# servo-ctrl.net
KiCad netlist of a schematic drawn in EAGLE
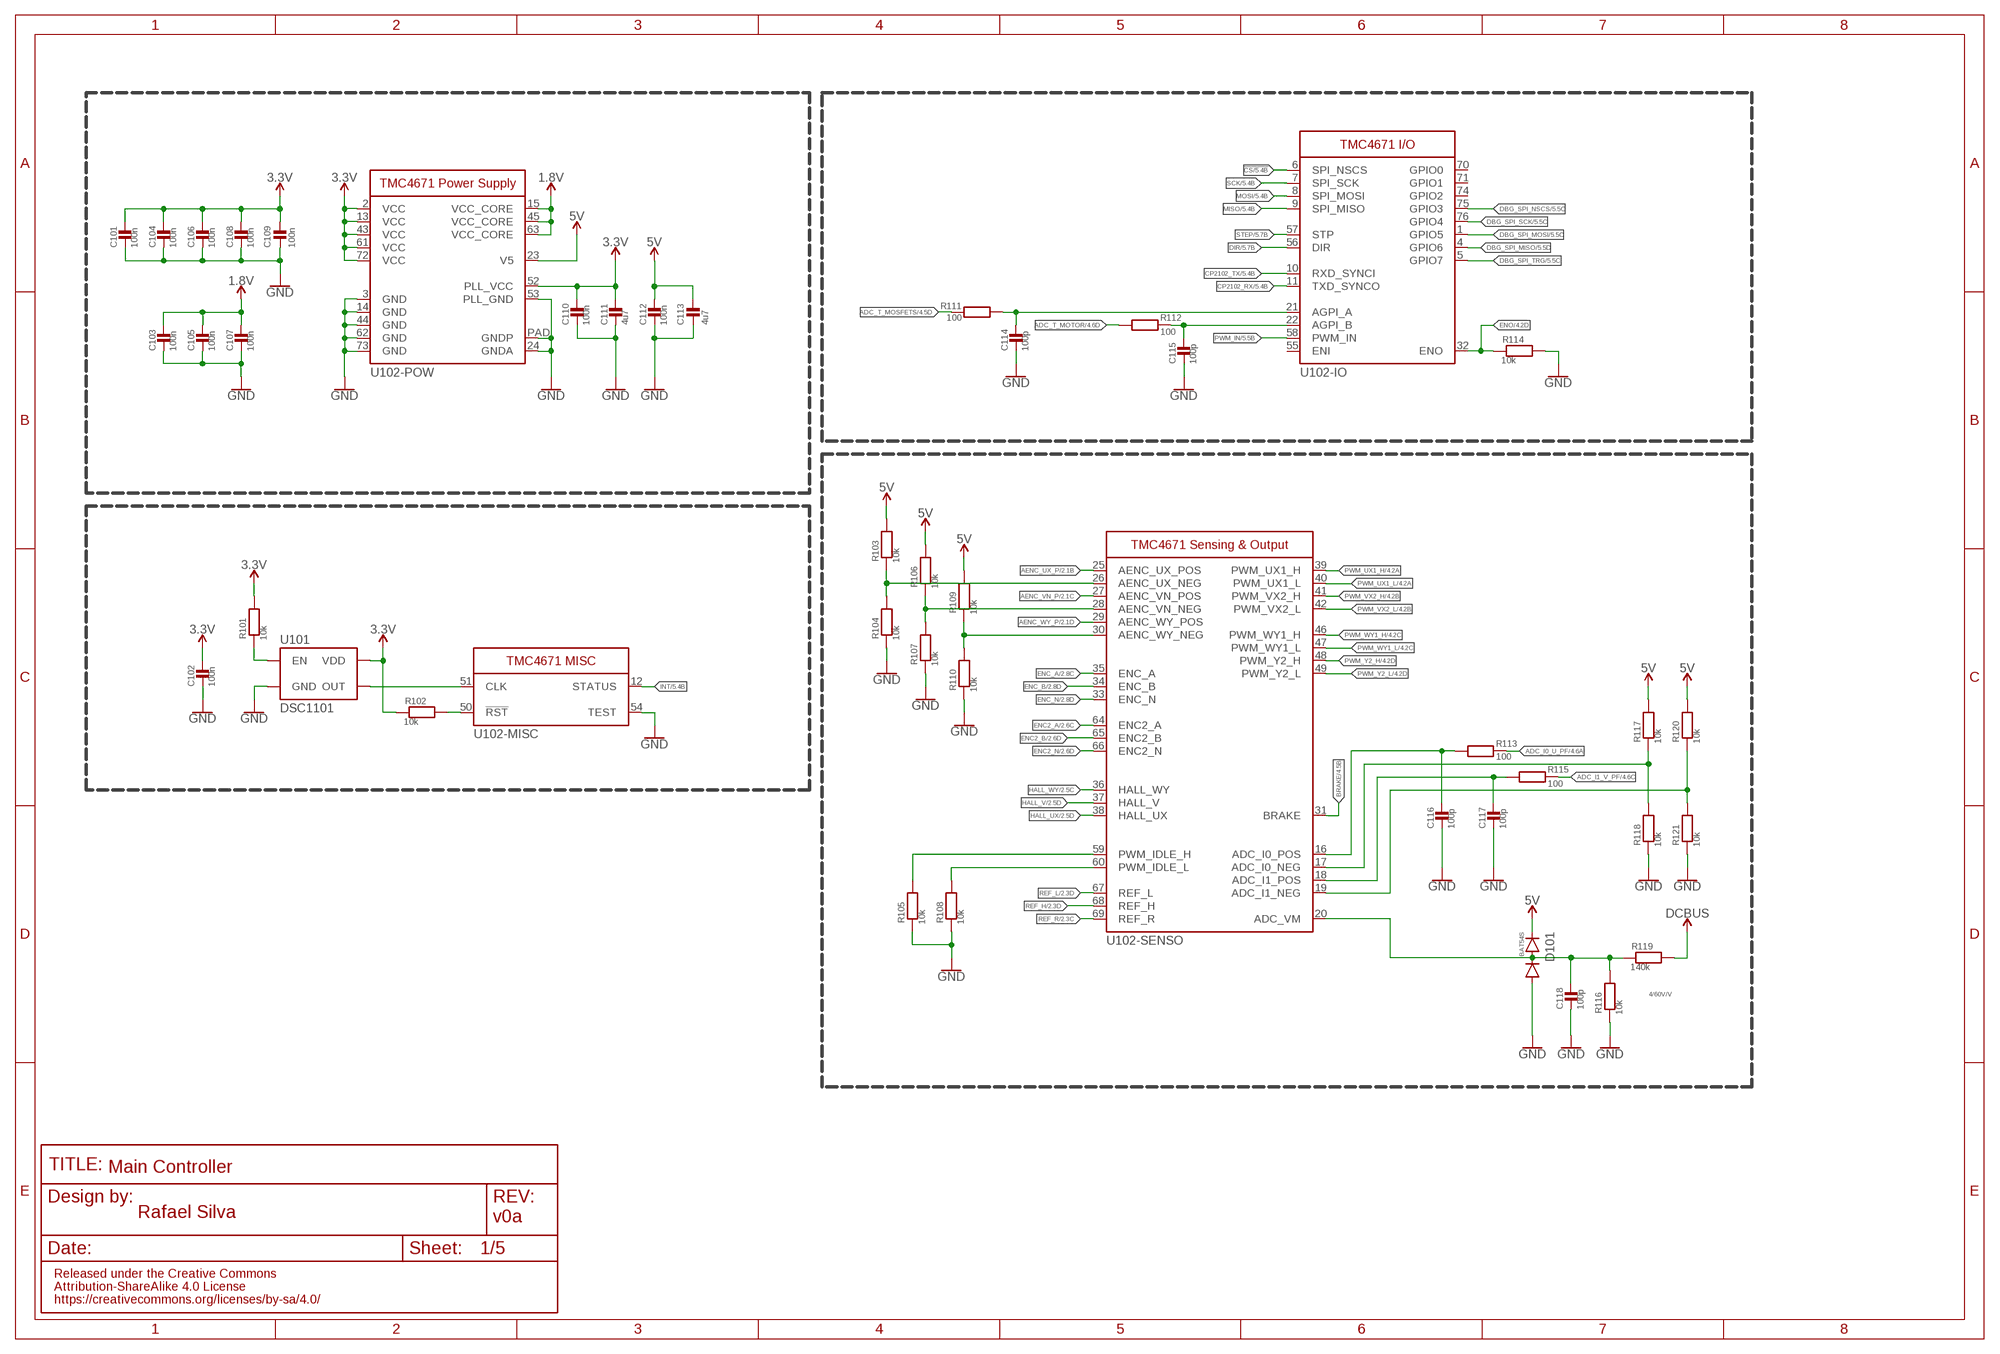
[diagram p0: schematic, sheet 1]
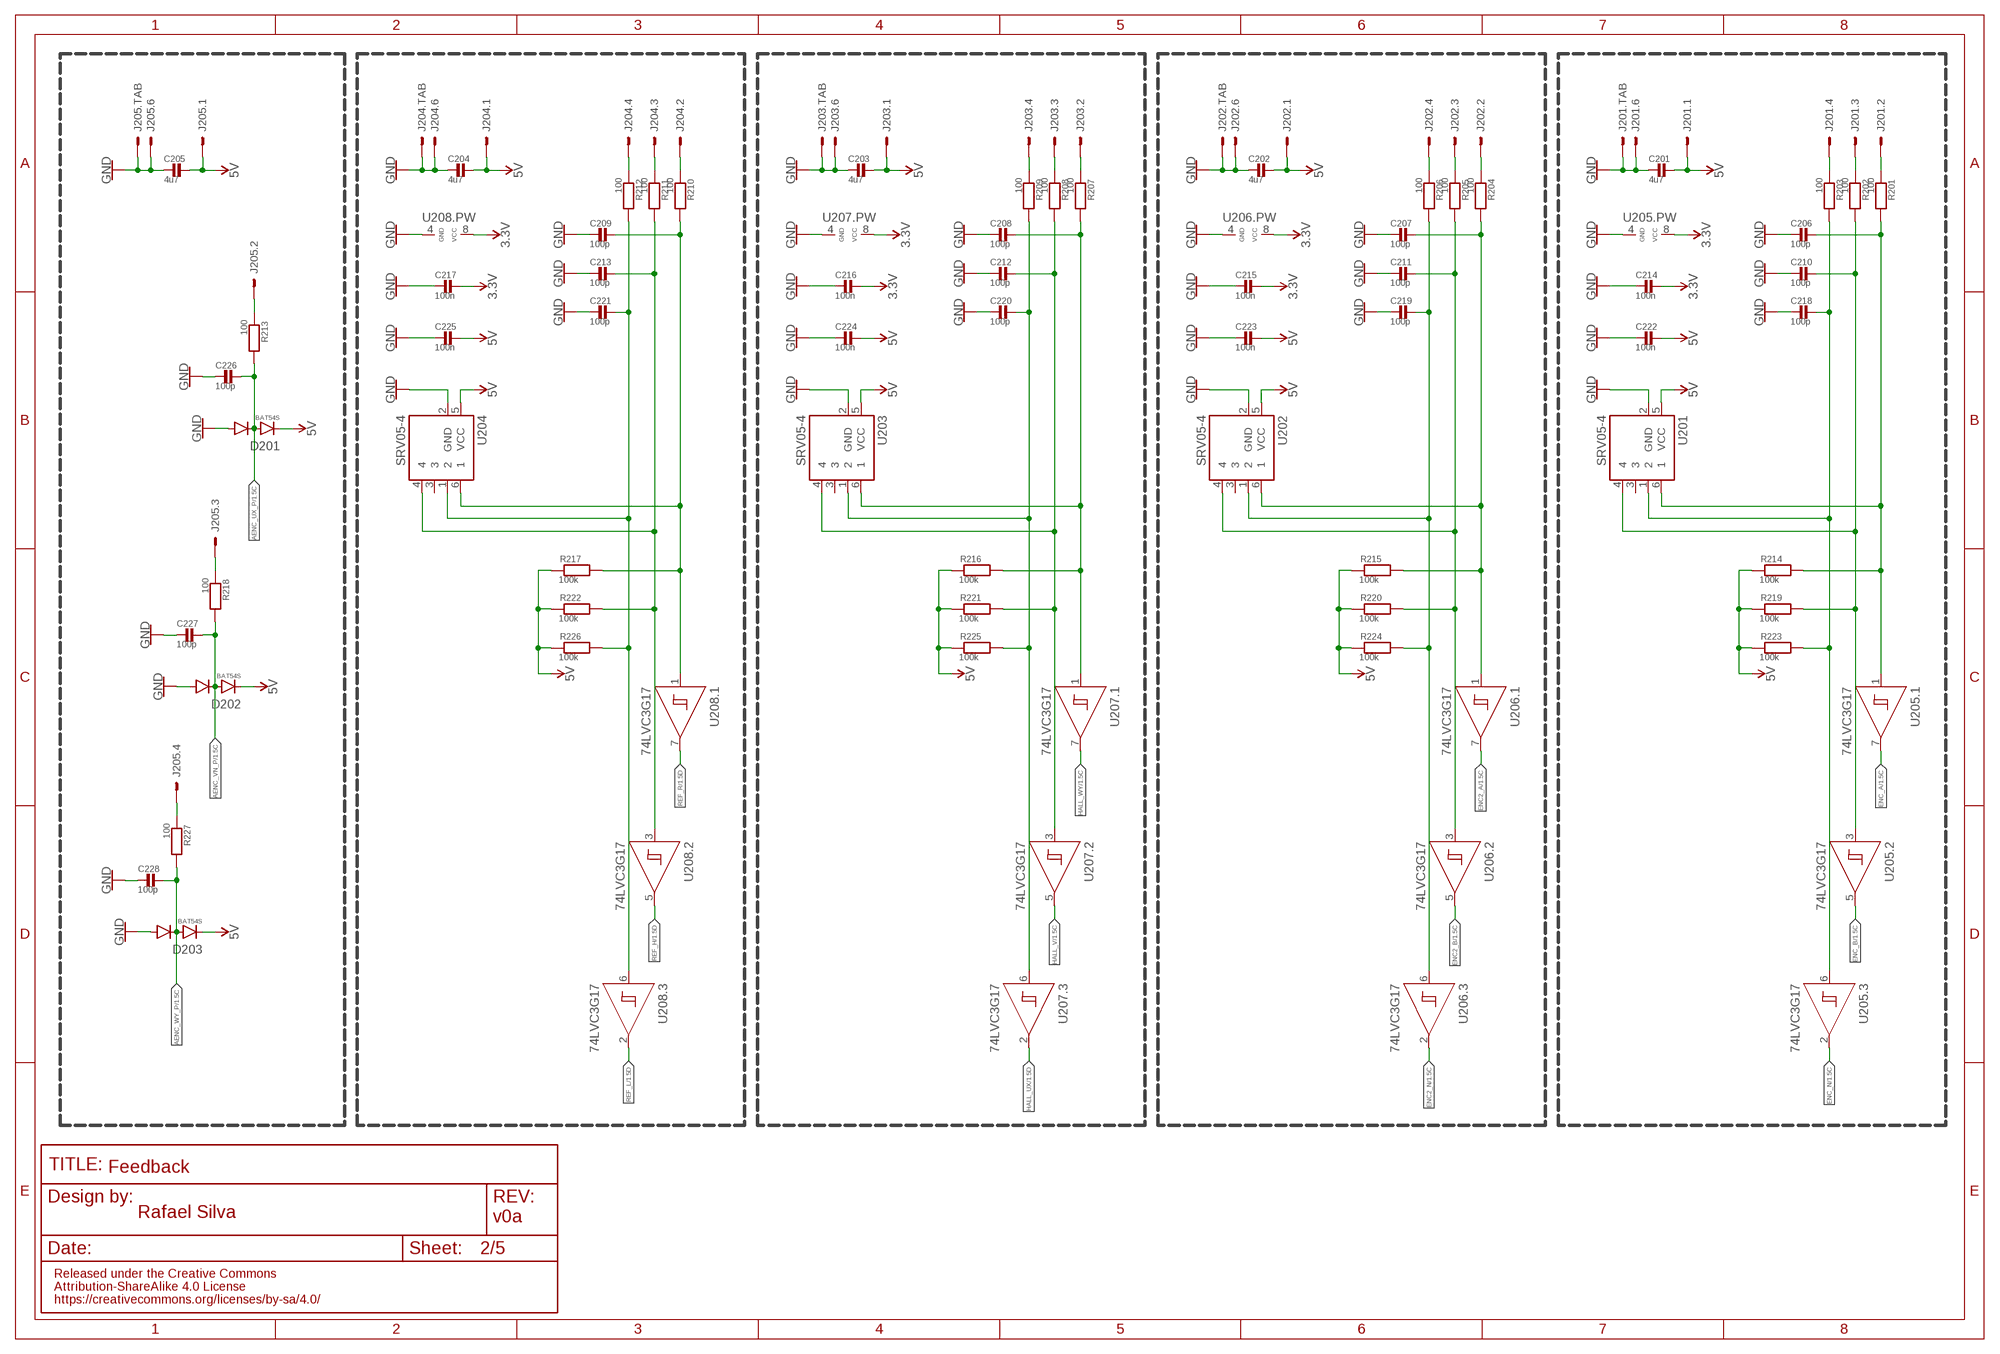
[diagram p1: schematic, sheet 2]
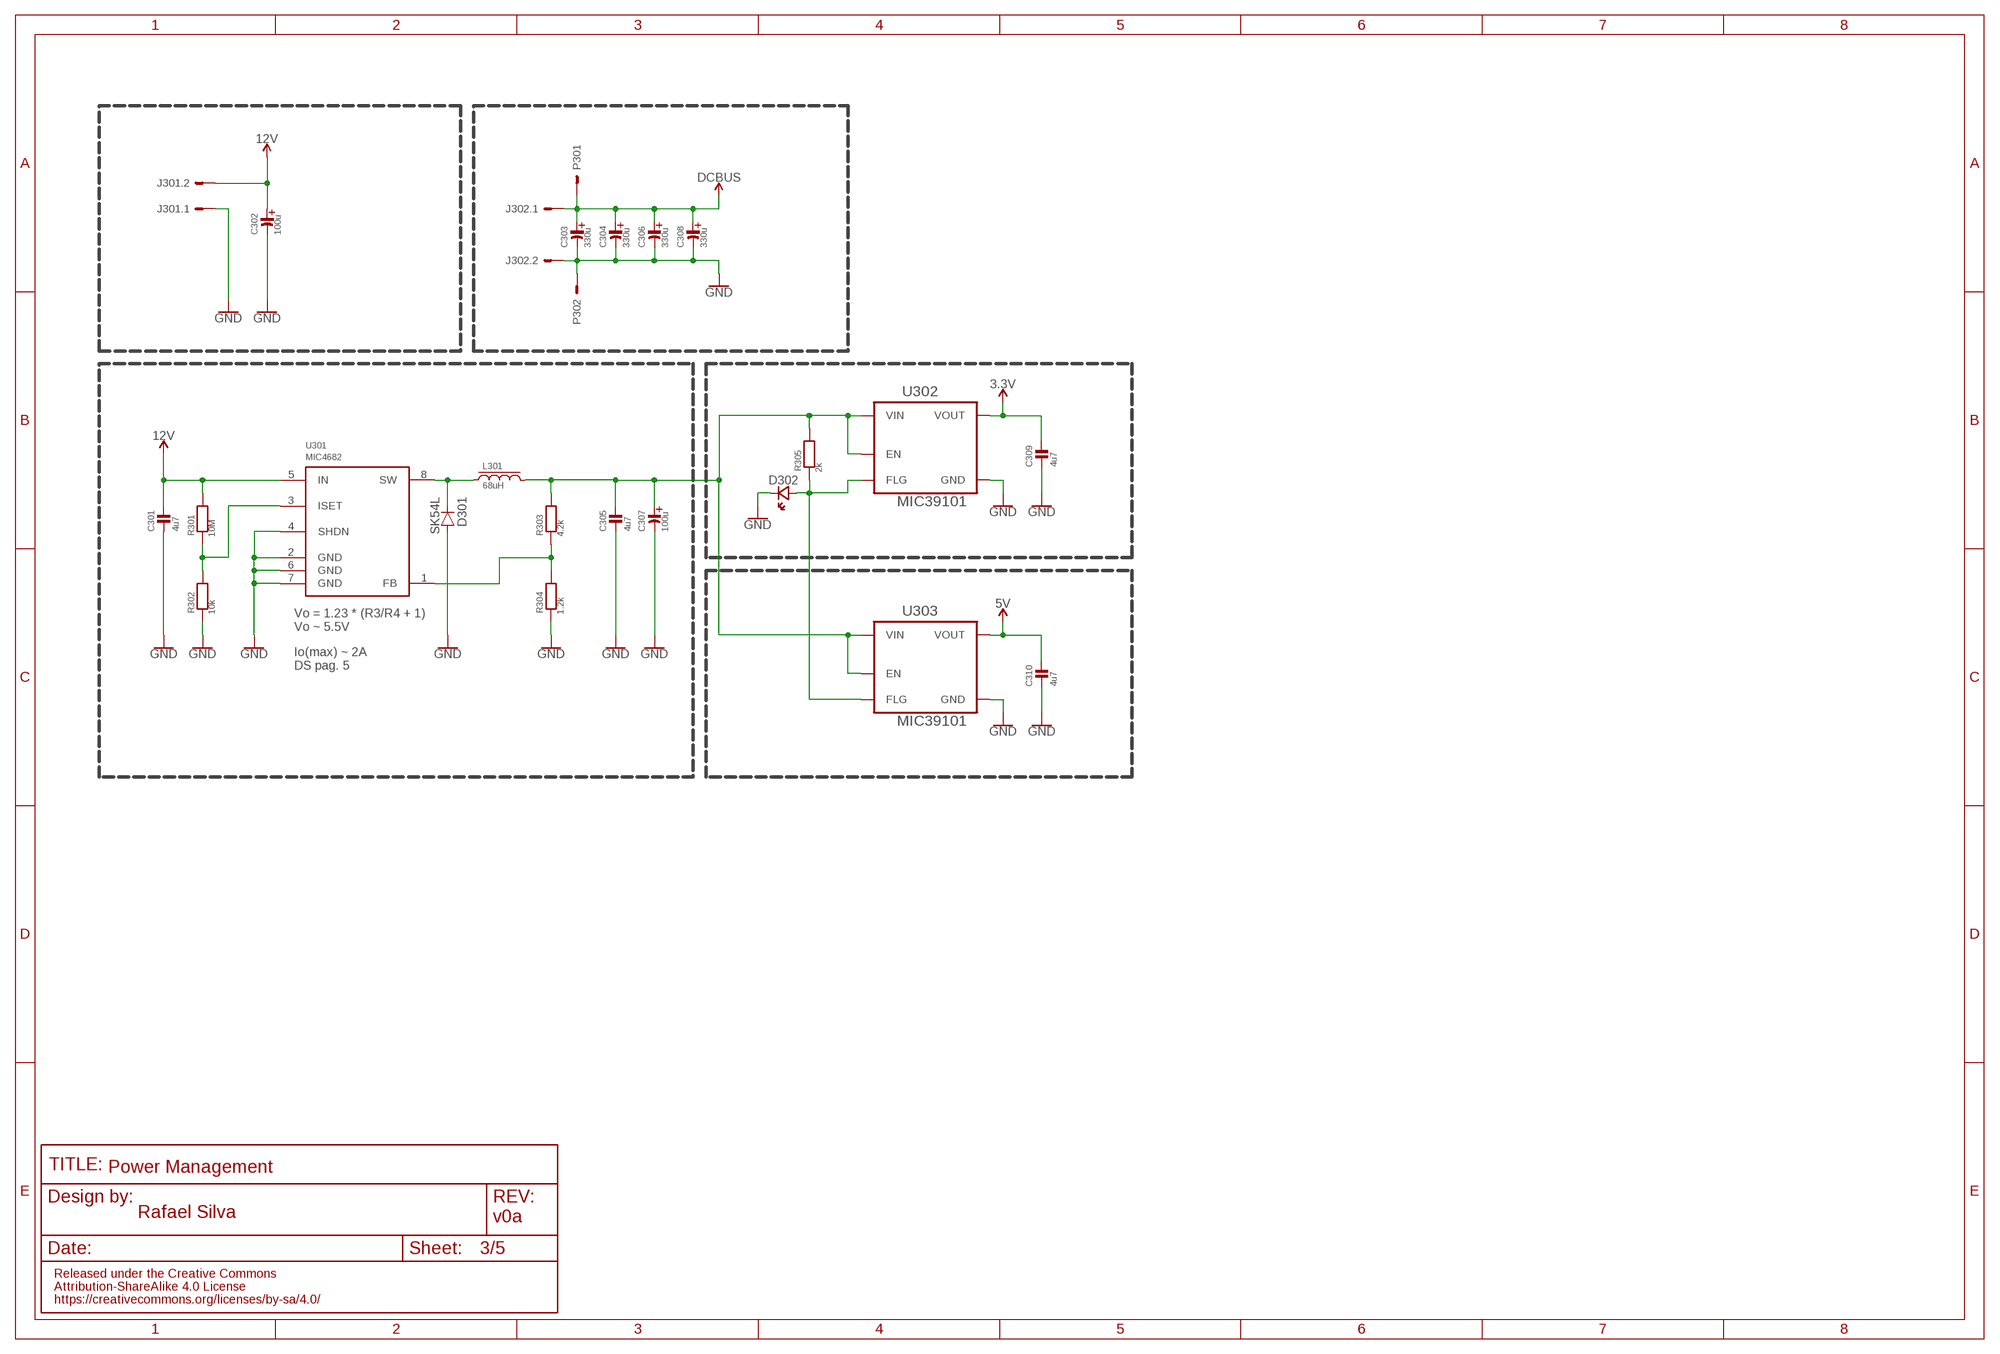
[diagram p2: schematic, sheet 3]
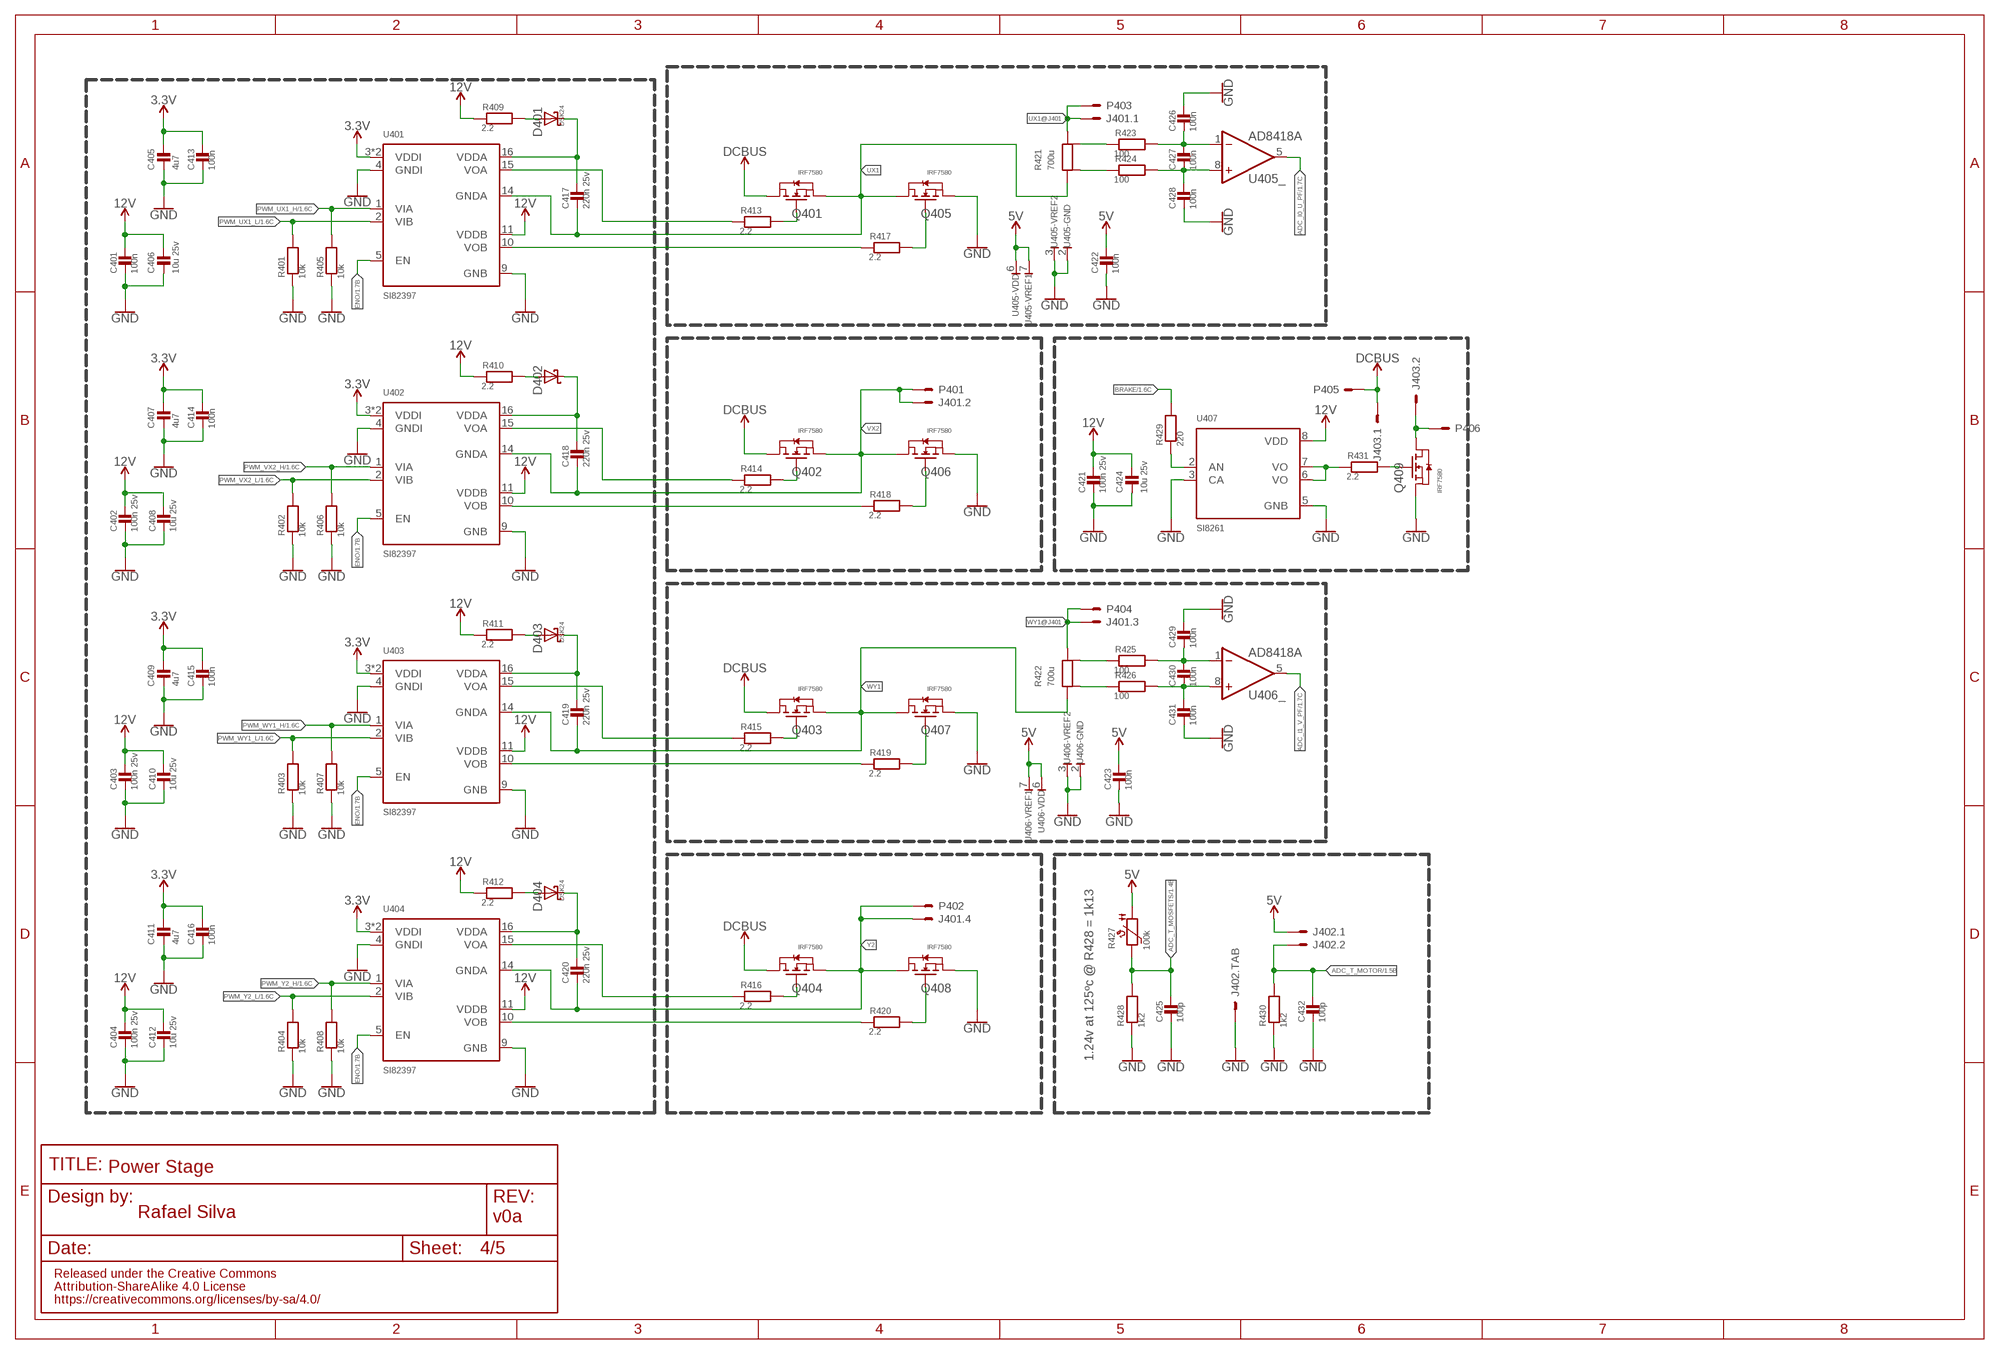
[diagram p3: schematic, sheet 4]
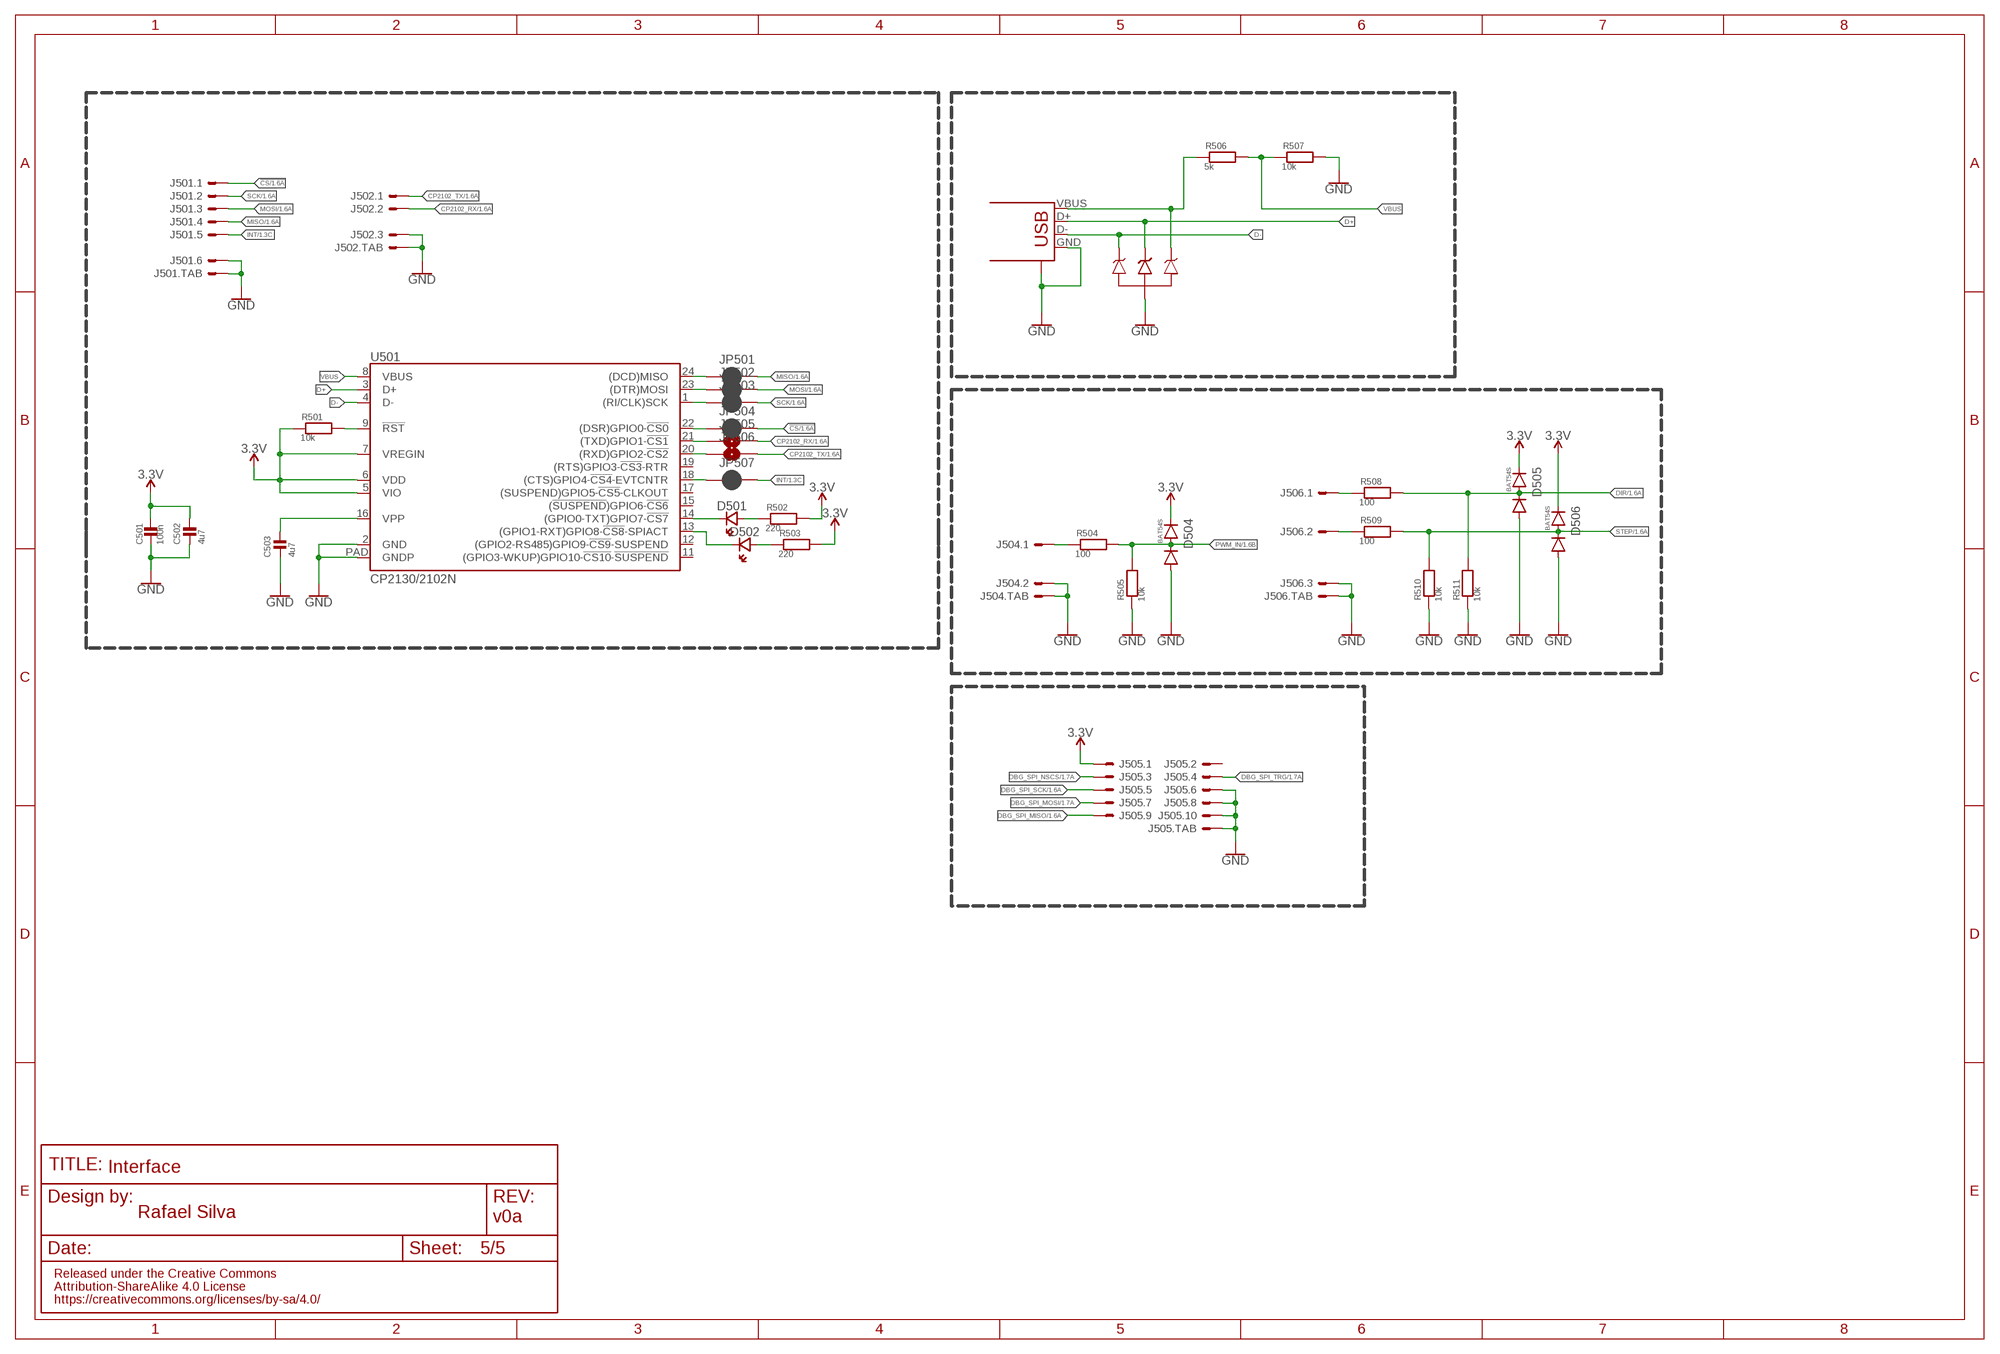
[diagram p4: schematic, sheet 5]

(export (version "E")
  (design (tool "Eeschema 10.0.6"))
  (components
    (comp (ref "C101")
      (value "100n")
      (footprint "eagle-import:0603_WAVE")
      (libsource (lib "eagle-import") (part "MLCC0603"))
    )
    (comp (ref "C102")
      (value "100n")
      (footprint "eagle-import:0603_WAVE")
      (libsource (lib "eagle-import") (part "MLCC0603"))
    )
    (comp (ref "C103")
      (value "100n")
      (footprint "eagle-import:0603_WAVE")
      (libsource (lib "eagle-import") (part "MLCC0603"))
    )
    (comp (ref "C104")
      (value "100n")
      (footprint "eagle-import:0603_WAVE")
      (libsource (lib "eagle-import") (part "MLCC0603"))
    )
    (comp (ref "C105")
      (value "100n")
      (footprint "eagle-import:0603_WAVE")
      (libsource (lib "eagle-import") (part "MLCC0603"))
    )
    (comp (ref "C106")
      (value "100n")
      (footprint "eagle-import:0603_WAVE")
      (libsource (lib "eagle-import") (part "MLCC0603"))
    )
    (comp (ref "C107")
      (value "100n")
      (footprint "eagle-import:0603_WAVE")
      (libsource (lib "eagle-import") (part "MLCC0603"))
    )
    (comp (ref "C108")
      (value "100n")
      (footprint "eagle-import:0603_WAVE")
      (libsource (lib "eagle-import") (part "MLCC0603"))
    )
    (comp (ref "C109")
      (value "100n")
      (footprint "eagle-import:0603_WAVE")
      (libsource (lib "eagle-import") (part "MLCC0603"))
    )
    (comp (ref "C110")
      (value "100n")
      (footprint "eagle-import:0603_WAVE")
      (libsource (lib "eagle-import") (part "MLCC0603"))
    )
    (comp (ref "C111")
      (value "4u7")
      (footprint "eagle-import:0603_WAVE")
      (libsource (lib "eagle-import") (part "MLCC0603"))
    )
    (comp (ref "C112")
      (value "100n")
      (footprint "eagle-import:0603_WAVE")
      (libsource (lib "eagle-import") (part "MLCC0603"))
    )
    (comp (ref "C113")
      (value "4u7")
      (footprint "eagle-import:0603_WAVE")
      (libsource (lib "eagle-import") (part "MLCC0603"))
    )
    (comp (ref "C114")
      (value "100p")
      (footprint "eagle-import:0603_WAVE")
      (libsource (lib "eagle-import") (part "MLCC0603"))
    )
    (comp (ref "C115")
      (value "100p")
      (footprint "eagle-import:0603_WAVE")
      (libsource (lib "eagle-import") (part "MLCC0603"))
    )
    (comp (ref "C116")
      (value "100p")
      (footprint "eagle-import:0603_WAVE")
      (libsource (lib "eagle-import") (part "MLCC0603"))
    )
    (comp (ref "C117")
      (value "100p")
      (footprint "eagle-import:0603_WAVE")
      (libsource (lib "eagle-import") (part "MLCC0603"))
    )
    (comp (ref "C118")
      (value "100p")
      (footprint "eagle-import:0603_WAVE")
      (libsource (lib "eagle-import") (part "MLCC0603"))
    )
    (comp (ref "D101")
      (value "BAT54S")
      (footprint "eagle-import:SOT-23-3")
      (libsource (lib "eagle-import") (part "BAT54S"))
    )
    (comp (ref "R101")
      (value "10k")
      (footprint "eagle-import:0603_WAVE")
      (libsource (lib "eagle-import") (part "RESISTOR0603"))
    )
    (comp (ref "R102")
      (value "10k")
      (footprint "eagle-import:0603_WAVE")
      (libsource (lib "eagle-import") (part "RESISTOR0603"))
    )
    (comp (ref "R103")
      (value "10k")
      (footprint "eagle-import:0603_WAVE")
      (libsource (lib "eagle-import") (part "RESISTOR0603"))
    )
    (comp (ref "R104")
      (value "10k")
      (footprint "eagle-import:0603_WAVE")
      (libsource (lib "eagle-import") (part "RESISTOR0603"))
    )
    (comp (ref "R105")
      (value "10k")
      (footprint "eagle-import:0603_WAVE")
      (libsource (lib "eagle-import") (part "RESISTOR0603"))
    )
    (comp (ref "R106")
      (value "10k")
      (footprint "eagle-import:0603_WAVE")
      (libsource (lib "eagle-import") (part "RESISTOR0603"))
    )
    (comp (ref "R107")
      (value "10k")
      (footprint "eagle-import:0603_WAVE")
      (libsource (lib "eagle-import") (part "RESISTOR0603"))
    )
    (comp (ref "R108")
      (value "10k")
      (footprint "eagle-import:0603_WAVE")
      (libsource (lib "eagle-import") (part "RESISTOR0603"))
    )
    (comp (ref "R109")
      (value "10k")
      (footprint "eagle-import:0603_WAVE")
      (libsource (lib "eagle-import") (part "RESISTOR0603"))
    )
    (comp (ref "R110")
      (value "10k")
      (footprint "eagle-import:0603_WAVE")
      (libsource (lib "eagle-import") (part "RESISTOR0603"))
    )
    (comp (ref "R111")
      (value "100")
      (footprint "eagle-import:0603_WAVE")
      (libsource (lib "eagle-import") (part "RESISTOR0603"))
    )
    (comp (ref "R112")
      (value "100")
      (footprint "eagle-import:0603_WAVE")
      (libsource (lib "eagle-import") (part "RESISTOR0603"))
    )
    (comp (ref "R113")
      (value "100")
      (footprint "eagle-import:0603_WAVE")
      (libsource (lib "eagle-import") (part "RESISTOR0603"))
    )
    (comp (ref "R114")
      (value "10k")
      (footprint "eagle-import:0603_WAVE")
      (libsource (lib "eagle-import") (part "RESISTOR0603"))
    )
    (comp (ref "R115")
      (value "100")
      (footprint "eagle-import:0603_WAVE")
      (libsource (lib "eagle-import") (part "RESISTOR0603"))
    )
    (comp (ref "R116")
      (value "10k")
      (footprint "eagle-import:0603_WAVE")
      (libsource (lib "eagle-import") (part "RESISTOR0603"))
    )
    (comp (ref "R117")
      (value "10k")
      (footprint "eagle-import:0603_WAVE")
      (libsource (lib "eagle-import") (part "RESISTOR0603"))
    )
    (comp (ref "R118")
      (value "10k")
      (footprint "eagle-import:0603_WAVE")
      (libsource (lib "eagle-import") (part "RESISTOR0603"))
    )
    (comp (ref "R119")
      (value "140k")
      (footprint "eagle-import:0603_WAVE")
      (libsource (lib "eagle-import") (part "RESISTOR0603"))
    )
    (comp (ref "R120")
      (value "10k")
      (footprint "eagle-import:0603_WAVE")
      (libsource (lib "eagle-import") (part "RESISTOR0603"))
    )
    (comp (ref "R121")
      (value "10k")
      (footprint "eagle-import:0603_WAVE")
      (libsource (lib "eagle-import") (part "RESISTOR0603"))
    )
    (comp (ref "U101")
      (value "DSC1101")
      (footprint "eagle-import:CDFN_5X3.2")
      (libsource (lib "eagle-import") (part "DSC1101"))
    )
    (comp (ref "U102")
      (value "TMC4671")
      (footprint "eagle-import:QFN76")
      (libsource (lib "eagle-import") (part "TMC4671"))
    )
    (comp (ref "C501")
      (value "100n")
      (footprint "eagle-import:0603_WAVE")
      (libsource (lib "eagle-import") (part "MLCC0603"))
    )
    (comp (ref "C502")
      (value "4u7")
      (footprint "eagle-import:0603_WAVE")
      (libsource (lib "eagle-import") (part "MLCC0603"))
    )
    (comp (ref "C503")
      (value "4u7")
      (footprint "eagle-import:0603_WAVE")
      (libsource (lib "eagle-import") (part "MLCC0603"))
    )
    (comp (ref "D501")
      (value "LED0603")
      (footprint "eagle-import:CHIPLED_0603")
      (libsource (lib "eagle-import") (part "LED0603"))
    )
    (comp (ref "D502")
      (value "LED0603")
      (footprint "eagle-import:CHIPLED_0603")
      (libsource (lib "eagle-import") (part "LED0603"))
    )
    (comp (ref "D503")
      (value "SP0503BAHT")
      (footprint "eagle-import:SOT143")
      (libsource (lib "eagle-import") (part "SP0503BAHT"))
    )
    (comp (ref "D504")
      (value "BAT54S")
      (footprint "eagle-import:SOT-23-3")
      (libsource (lib "eagle-import") (part "BAT54S"))
    )
    (comp (ref "D505")
      (value "BAT54S")
      (footprint "eagle-import:SOT-23-3")
      (libsource (lib "eagle-import") (part "BAT54S"))
    )
    (comp (ref "D506")
      (value "BAT54S")
      (footprint "eagle-import:SOT-23-3")
      (libsource (lib "eagle-import") (part "BAT54S"))
    )
    (comp (ref "J501")
      (value "SH-6")
      (footprint "eagle-import:SM06B-SSR-H-TB")
      (libsource (lib "eagle-import") (part "SH-6"))
    )
    (comp (ref "J502")
      (value "SH-3")
      (footprint "eagle-import:SM03B-SSR-H-TB")
      (libsource (lib "eagle-import") (part "SH-3"))
    )
    (comp (ref "J503")
      (value "USB-SHIELD")
      (footprint "eagle-import:USB-M-S1")
      (libsource (lib "eagle-import") (part "USB-SHIELD"))
    )
    (comp (ref "J504")
      (value "SH-2")
      (footprint "eagle-import:SM02B-SSR-H-TB")
      (libsource (lib "eagle-import") (part "SH-2"))
    )
    (comp (ref "J505")
      (value "F20F-10DP-1V")
      (footprint "eagle-import:F20F-10DP-1V")
      (libsource (lib "eagle-import") (part "F20F-10DP-1V"))
    )
    (comp (ref "J506")
      (value "SH-3")
      (footprint "eagle-import:SM03B-SSR-H-TB")
      (libsource (lib "eagle-import") (part "SH-3"))
    )
    (comp (ref "JP501")
      (value "JUMPER-SMT_2_NC_PASTE_SILK")
      (footprint "eagle-import:SMT-JUMPER_2_NC_PASTE_SILK")
      (libsource (lib "eagle-import") (part "JUMPER-SMT_2_NC_PASTE_SILK"))
    )
    (comp (ref "JP502")
      (value "JUMPER-SMT_2_NC_PASTE_SILK")
      (footprint "eagle-import:SMT-JUMPER_2_NC_PASTE_SILK")
      (libsource (lib "eagle-import") (part "JUMPER-SMT_2_NC_PASTE_SILK"))
    )
    (comp (ref "JP503")
      (value "JUMPER-SMT_2_NC_PASTE_SILK")
      (footprint "eagle-import:SMT-JUMPER_2_NC_PASTE_SILK")
      (libsource (lib "eagle-import") (part "JUMPER-SMT_2_NC_PASTE_SILK"))
    )
    (comp (ref "JP504")
      (value "JUMPER-SMT_2_NC_PASTE_SILK")
      (footprint "eagle-import:SMT-JUMPER_2_NC_PASTE_SILK")
      (libsource (lib "eagle-import") (part "JUMPER-SMT_2_NC_PASTE_SILK"))
    )
    (comp (ref "JP505")
      (value "JUMPER-SMT_2_NO_SILK")
      (footprint "eagle-import:SMT-JUMPER_2_NO_SILK")
      (libsource (lib "eagle-import") (part "JUMPER-SMT_2_NO_SILK"))
    )
    (comp (ref "JP506")
      (value "JUMPER-SMT_2_NO_SILK")
      (footprint "eagle-import:SMT-JUMPER_2_NO_SILK")
      (libsource (lib "eagle-import") (part "JUMPER-SMT_2_NO_SILK"))
    )
    (comp (ref "JP507")
      (value "JUMPER-SMT_2_NC_PASTE_SILK")
      (footprint "eagle-import:SMT-JUMPER_2_NC_PASTE_SILK")
      (libsource (lib "eagle-import") (part "JUMPER-SMT_2_NC_PASTE_SILK"))
    )
    (comp (ref "R501")
      (value "10k")
      (footprint "eagle-import:0603_WAVE")
      (libsource (lib "eagle-import") (part "RESISTOR0603"))
    )
    (comp (ref "R502")
      (value "220")
      (footprint "eagle-import:0603_WAVE")
      (libsource (lib "eagle-import") (part "RESISTOR0603"))
    )
    (comp (ref "R503")
      (value "220")
      (footprint "eagle-import:0603_WAVE")
      (libsource (lib "eagle-import") (part "RESISTOR0603"))
    )
    (comp (ref "R504")
      (value "100")
      (footprint "eagle-import:0603_WAVE")
      (libsource (lib "eagle-import") (part "RESISTOR0603"))
    )
    (comp (ref "R505")
      (value "10k")
      (footprint "eagle-import:0603_WAVE")
      (libsource (lib "eagle-import") (part "RESISTOR0603"))
    )
    (comp (ref "R506")
      (value "5k")
      (footprint "eagle-import:0603_WAVE")
      (libsource (lib "eagle-import") (part "RESISTOR0603"))
    )
    (comp (ref "R507")
      (value "10k")
      (footprint "eagle-import:0603_WAVE")
      (libsource (lib "eagle-import") (part "RESISTOR0603"))
    )
    (comp (ref "R508")
      (value "100")
      (footprint "eagle-import:0603_WAVE")
      (libsource (lib "eagle-import") (part "RESISTOR0603"))
    )
    (comp (ref "R509")
      (value "100")
      (footprint "eagle-import:0603_WAVE")
      (libsource (lib "eagle-import") (part "RESISTOR0603"))
    )
    (comp (ref "R510")
      (value "10k")
      (footprint "eagle-import:0603_WAVE")
      (libsource (lib "eagle-import") (part "RESISTOR0603"))
    )
    (comp (ref "R511")
      (value "10k")
      (footprint "eagle-import:0603_WAVE")
      (libsource (lib "eagle-import") (part "RESISTOR0603"))
    )
    (comp (ref "U501")
      (value "CP2130/2102N")
      (footprint "eagle-import:QFN24")
      (libsource (lib "eagle-import") (part "CP2130/2102N"))
    )
    (comp (ref "C401")
      (value "100n")
      (footprint "eagle-import:0603_WAVE")
      (libsource (lib "eagle-import") (part "MLCC0603"))
    )
    (comp (ref "C402")
      (value "100n 25v")
      (footprint "eagle-import:0603_WAVE")
      (libsource (lib "eagle-import") (part "MLCC0603"))
    )
    (comp (ref "C403")
      (value "100n 25v")
      (footprint "eagle-import:0603_WAVE")
      (libsource (lib "eagle-import") (part "MLCC0603"))
    )
    (comp (ref "C404")
      (value "100n 25v")
      (footprint "eagle-import:0603_WAVE")
      (libsource (lib "eagle-import") (part "MLCC0603"))
    )
    (comp (ref "C405")
      (value "4u7")
      (footprint "eagle-import:0603_WAVE")
      (libsource (lib "eagle-import") (part "MLCC0603"))
    )
    (comp (ref "C406")
      (value "10u 25v")
      (footprint "eagle-import:0603_WAVE")
      (libsource (lib "eagle-import") (part "MLCC0603"))
    )
    (comp (ref "C407")
      (value "4u7")
      (footprint "eagle-import:0603_WAVE")
      (libsource (lib "eagle-import") (part "MLCC0603"))
    )
    (comp (ref "C408")
      (value "10u 25v")
      (footprint "eagle-import:0603_WAVE")
      (libsource (lib "eagle-import") (part "MLCC0603"))
    )
    (comp (ref "C409")
      (value "4u7")
      (footprint "eagle-import:0603_WAVE")
      (libsource (lib "eagle-import") (part "MLCC0603"))
    )
    (comp (ref "C410")
      (value "10u 25v")
      (footprint "eagle-import:0603_WAVE")
      (libsource (lib "eagle-import") (part "MLCC0603"))
    )
    (comp (ref "C411")
      (value "4u7")
      (footprint "eagle-import:0603_WAVE")
      (libsource (lib "eagle-import") (part "MLCC0603"))
    )
    (comp (ref "C412")
      (value "10u 25v")
      (footprint "eagle-import:0603_WAVE")
      (libsource (lib "eagle-import") (part "MLCC0603"))
    )
    (comp (ref "C413")
      (value "100n")
      (footprint "eagle-import:0603_WAVE")
      (libsource (lib "eagle-import") (part "MLCC0603"))
    )
    (comp (ref "C414")
      (value "100n")
      (footprint "eagle-import:0603_WAVE")
      (libsource (lib "eagle-import") (part "MLCC0603"))
    )
    (comp (ref "C415")
      (value "100n")
      (footprint "eagle-import:0603_WAVE")
      (libsource (lib "eagle-import") (part "MLCC0603"))
    )
    (comp (ref "C416")
      (value "100n")
      (footprint "eagle-import:0603_WAVE")
      (libsource (lib "eagle-import") (part "MLCC0603"))
    )
    (comp (ref "C417")
      (value "220n 25v")
      (footprint "eagle-import:0603_WAVE")
      (libsource (lib "eagle-import") (part "MLCC0603"))
    )
    (comp (ref "C418")
      (value "220n 25v")
      (footprint "eagle-import:0603_WAVE")
      (libsource (lib "eagle-import") (part "MLCC0603"))
    )
    (comp (ref "C419")
      (value "220n 25v")
      (footprint "eagle-import:0603_WAVE")
      (libsource (lib "eagle-import") (part "MLCC0603"))
    )
    (comp (ref "C420")
      (value "220n 25v")
      (footprint "eagle-import:0603_WAVE")
      (libsource (lib "eagle-import") (part "MLCC0603"))
    )
    (comp (ref "C421")
      (value "100n 25v")
      (footprint "eagle-import:0603_WAVE")
      (libsource (lib "eagle-import") (part "MLCC0603"))
    )
    (comp (ref "C422")
      (value "100n")
      (footprint "eagle-import:0603_WAVE")
      (libsource (lib "eagle-import") (part "MLCC0603"))
    )
    (comp (ref "C423")
      (value "100n")
      (footprint "eagle-import:0603_WAVE")
      (libsource (lib "eagle-import") (part "MLCC0603"))
    )
    (comp (ref "C424")
      (value "10u 25v")
      (footprint "eagle-import:0603_WAVE")
      (libsource (lib "eagle-import") (part "MLCC0603"))
    )
    (comp (ref "C425")
      (value "100p")
      (footprint "eagle-import:0603_WAVE")
      (libsource (lib "eagle-import") (part "MLCC0603"))
    )
    (comp (ref "C426")
      (value "100n")
      (footprint "eagle-import:0603_WAVE")
      (libsource (lib "eagle-import") (part "MLCC0603"))
    )
    (comp (ref "C427")
      (value "100n")
      (footprint "eagle-import:0603_WAVE")
      (libsource (lib "eagle-import") (part "MLCC0603"))
    )
    (comp (ref "C428")
      (value "100n")
      (footprint "eagle-import:0603_WAVE")
      (libsource (lib "eagle-import") (part "MLCC0603"))
    )
    (comp (ref "C429")
      (value "100n")
      (footprint "eagle-import:0603_WAVE")
      (libsource (lib "eagle-import") (part "MLCC0603"))
    )
    (comp (ref "C430")
      (value "100n")
      (footprint "eagle-import:0603_WAVE")
      (libsource (lib "eagle-import") (part "MLCC0603"))
    )
    (comp (ref "C431")
      (value "100n")
      (footprint "eagle-import:0603_WAVE")
      (libsource (lib "eagle-import") (part "MLCC0603"))
    )
    (comp (ref "C432")
      (value "100p")
      (footprint "eagle-import:0603_WAVE")
      (libsource (lib "eagle-import") (part "MLCC0603"))
    )
    (comp (ref "D401")
      (value "DSK24")
      (footprint "eagle-import:SOD-123")
      (libsource (lib "eagle-import") (part "DSK24"))
    )
    (comp (ref "D402")
      (value "DSK24")
      (footprint "eagle-import:SOD-123")
      (libsource (lib "eagle-import") (part "DSK24"))
    )
    (comp (ref "D403")
      (value "DSK24")
      (footprint "eagle-import:SOD-123")
      (libsource (lib "eagle-import") (part "DSK24"))
    )
    (comp (ref "D404")
      (value "DSK24")
      (footprint "eagle-import:SOD-123")
      (libsource (lib "eagle-import") (part "DSK24"))
    )
    (comp (ref "J401")
      (value "4P-6.35P")
      (footprint "eagle-import:4P-6.35P")
      (libsource (lib "eagle-import") (part "4P-6.35P"))
    )
    (comp (ref "J402")
      (value "SH-2")
      (footprint "eagle-import:SM02B-SSR-H-TB")
      (libsource (lib "eagle-import") (part "SH-2"))
    )
    (comp (ref "J403")
      (value "2P-6.35P")
      (footprint "eagle-import:2P-6.35P")
      (libsource (lib "eagle-import") (part "2P-6.35P"))
    )
    (comp (ref "P401")
      (value "POWPAD")
      (footprint "eagle-import:TH-HP")
      (libsource (lib "eagle-import") (part "POWPAD"))
    )
    (comp (ref "P402")
      (value "POWPAD")
      (footprint "eagle-import:TH-HP")
      (libsource (lib "eagle-import") (part "POWPAD"))
    )
    (comp (ref "P403")
      (value "POWPAD")
      (footprint "eagle-import:TH-HP")
      (libsource (lib "eagle-import") (part "POWPAD"))
    )
    (comp (ref "P404")
      (value "POWPAD")
      (footprint "eagle-import:TH-HP")
      (libsource (lib "eagle-import") (part "POWPAD"))
    )
    (comp (ref "P405")
      (value "POWPAD")
      (footprint "eagle-import:TH-HP")
      (libsource (lib "eagle-import") (part "POWPAD"))
    )
    (comp (ref "P406")
      (value "POWPAD")
      (footprint "eagle-import:TH-HP")
      (libsource (lib "eagle-import") (part "POWPAD"))
    )
    (comp (ref "Q401")
      (value "IRF7580")
      (footprint "eagle-import:DIRECTFET-ME")
      (libsource (lib "eagle-import") (part "IRF7580"))
    )
    (comp (ref "Q402")
      (value "IRF7580")
      (footprint "eagle-import:DIRECTFET-ME")
      (libsource (lib "eagle-import") (part "IRF7580"))
    )
    (comp (ref "Q403")
      (value "IRF7580")
      (footprint "eagle-import:DIRECTFET-ME")
      (libsource (lib "eagle-import") (part "IRF7580"))
    )
    (comp (ref "Q404")
      (value "IRF7580")
      (footprint "eagle-import:DIRECTFET-ME")
      (libsource (lib "eagle-import") (part "IRF7580"))
    )
    (comp (ref "Q405")
      (value "IRF7580")
      (footprint "eagle-import:DIRECTFET-ME")
      (libsource (lib "eagle-import") (part "IRF7580"))
    )
    (comp (ref "Q406")
      (value "IRF7580")
      (footprint "eagle-import:DIRECTFET-ME")
      (libsource (lib "eagle-import") (part "IRF7580"))
    )
    (comp (ref "Q407")
      (value "IRF7580")
      (footprint "eagle-import:DIRECTFET-ME")
      (libsource (lib "eagle-import") (part "IRF7580"))
    )
    (comp (ref "Q408")
      (value "IRF7580")
      (footprint "eagle-import:DIRECTFET-ME")
      (libsource (lib "eagle-import") (part "IRF7580"))
    )
    (comp (ref "Q409")
      (value "IRF7580")
      (footprint "eagle-import:DIRECTFET-ME")
      (libsource (lib "eagle-import") (part "IRF7580"))
    )
    (comp (ref "R401")
      (value "10k")
      (footprint "eagle-import:0603_WAVE")
      (libsource (lib "eagle-import") (part "RESISTOR0603"))
    )
    (comp (ref "R402")
      (value "10k")
      (footprint "eagle-import:0603_WAVE")
      (libsource (lib "eagle-import") (part "RESISTOR0603"))
    )
    (comp (ref "R403")
      (value "10k")
      (footprint "eagle-import:0603_WAVE")
      (libsource (lib "eagle-import") (part "RESISTOR0603"))
    )
    (comp (ref "R404")
      (value "10k")
      (footprint "eagle-import:0603_WAVE")
      (libsource (lib "eagle-import") (part "RESISTOR0603"))
    )
    (comp (ref "R405")
      (value "10k")
      (footprint "eagle-import:0603_WAVE")
      (libsource (lib "eagle-import") (part "RESISTOR0603"))
    )
    (comp (ref "R406")
      (value "10k")
      (footprint "eagle-import:0603_WAVE")
      (libsource (lib "eagle-import") (part "RESISTOR0603"))
    )
    (comp (ref "R407")
      (value "10k")
      (footprint "eagle-import:0603_WAVE")
      (libsource (lib "eagle-import") (part "RESISTOR0603"))
    )
    (comp (ref "R408")
      (value "10k")
      (footprint "eagle-import:0603_WAVE")
      (libsource (lib "eagle-import") (part "RESISTOR0603"))
    )
    (comp (ref "R409")
      (value "2.2")
      (footprint "eagle-import:0603_WAVE")
      (libsource (lib "eagle-import") (part "RESISTOR0603"))
    )
    (comp (ref "R410")
      (value "2.2")
      (footprint "eagle-import:0603_WAVE")
      (libsource (lib "eagle-import") (part "RESISTOR0603"))
    )
    (comp (ref "R411")
      (value "2.2")
      (footprint "eagle-import:0603_WAVE")
      (libsource (lib "eagle-import") (part "RESISTOR0603"))
    )
    (comp (ref "R412")
      (value "2.2")
      (footprint "eagle-import:0603_WAVE")
      (libsource (lib "eagle-import") (part "RESISTOR0603"))
    )
    (comp (ref "R413")
      (value "2.2")
      (footprint "eagle-import:0603_WAVE")
      (libsource (lib "eagle-import") (part "RESISTOR0603"))
    )
    (comp (ref "R414")
      (value "2.2")
      (footprint "eagle-import:0603_WAVE")
      (libsource (lib "eagle-import") (part "RESISTOR0603"))
    )
    (comp (ref "R415")
      (value "2.2")
      (footprint "eagle-import:0603_WAVE")
      (libsource (lib "eagle-import") (part "RESISTOR0603"))
    )
    (comp (ref "R416")
      (value "2.2")
      (footprint "eagle-import:0603_WAVE")
      (libsource (lib "eagle-import") (part "RESISTOR0603"))
    )
    (comp (ref "R417")
      (value "2.2")
      (footprint "eagle-import:0603_WAVE")
      (libsource (lib "eagle-import") (part "RESISTOR0603"))
    )
    (comp (ref "R418")
      (value "2.2")
      (footprint "eagle-import:0603_WAVE")
      (libsource (lib "eagle-import") (part "RESISTOR0603"))
    )
    (comp (ref "R419")
      (value "2.2")
      (footprint "eagle-import:0603_WAVE")
      (libsource (lib "eagle-import") (part "RESISTOR0603"))
    )
    (comp (ref "R420")
      (value "2.2")
      (footprint "eagle-import:0603_WAVE")
      (libsource (lib "eagle-import") (part "RESISTOR0603"))
    )
    (comp (ref "R421")
      (value "700u")
      (footprint "eagle-import:3920")
      (libsource (lib "eagle-import") (part "LRMAP3920"))
    )
    (comp (ref "R422")
      (value "700u")
      (footprint "eagle-import:3920")
      (libsource (lib "eagle-import") (part "LRMAP3920"))
    )
    (comp (ref "R423")
      (value "100")
      (footprint "eagle-import:0603_WAVE")
      (libsource (lib "eagle-import") (part "RESISTOR0603"))
    )
    (comp (ref "R424")
      (value "100")
      (footprint "eagle-import:0603_WAVE")
      (libsource (lib "eagle-import") (part "RESISTOR0603"))
    )
    (comp (ref "R425")
      (value "100")
      (footprint "eagle-import:0603_WAVE")
      (libsource (lib "eagle-import") (part "RESISTOR0603"))
    )
    (comp (ref "R426")
      (value "100")
      (footprint "eagle-import:0603_WAVE")
      (libsource (lib "eagle-import") (part "RESISTOR0603"))
    )
    (comp (ref "R427")
      (value "100k")
      (footprint "eagle-import:0603_WAVE")
      (libsource (lib "eagle-import") (part "NTC0603"))
    )
    (comp (ref "R428")
      (value "1k2")
      (footprint "eagle-import:0603_WAVE")
      (libsource (lib "eagle-import") (part "RESISTOR0603"))
    )
    (comp (ref "R429")
      (value "220")
      (footprint "eagle-import:0603_WAVE")
      (libsource (lib "eagle-import") (part "RESISTOR0603"))
    )
    (comp (ref "R430")
      (value "1k2")
      (footprint "eagle-import:0603_WAVE")
      (libsource (lib "eagle-import") (part "RESISTOR0603"))
    )
    (comp (ref "R431")
      (value "2.2")
      (footprint "eagle-import:0603_WAVE")
      (libsource (lib "eagle-import") (part "RESISTOR0603"))
    )
    (comp (ref "U401")
      (value "SI82397")
      (footprint "eagle-import:SOIC-16-WB")
      (libsource (lib "eagle-import") (part "SI82397"))
    )
    (comp (ref "U402")
      (value "SI82397")
      (footprint "eagle-import:SOIC-16-WB")
      (libsource (lib "eagle-import") (part "SI82397"))
    )
    (comp (ref "U403")
      (value "SI82397")
      (footprint "eagle-import:SOIC-16-WB")
      (libsource (lib "eagle-import") (part "SI82397"))
    )
    (comp (ref "U404")
      (value "SI82397")
      (footprint "eagle-import:SOIC-16-WB")
      (libsource (lib "eagle-import") (part "SI82397"))
    )
    (comp (ref "U405")
      (value "AD8418A")
      (footprint "eagle-import:MSOP-8")
      (libsource (lib "eagle-import") (part "AD8418A"))
    )
    (comp (ref "U406")
      (value "AD8418A")
      (footprint "eagle-import:MSOP-8")
      (libsource (lib "eagle-import") (part "AD8418A"))
    )
    (comp (ref "U407")
      (value "SI8261")
      (footprint "eagle-import:SOIC_8")
      (libsource (lib "eagle-import") (part "SI8261"))
    )
    (comp (ref "C301")
      (value "4u7")
      (footprint "eagle-import:0603_WAVE")
      (libsource (lib "eagle-import") (part "MLCC0603"))
    )
    (comp (ref "C302")
      (value "100u")
      (footprint "eagle-import:PANASONIC_D")
      (libsource (lib "eagle-import") (part "CAPACITOR_ELD"))
    )
    (comp (ref "C303")
      (value "330u")
      (footprint "eagle-import:PANASONIC_G")
      (libsource (lib "eagle-import") (part "CAPACITOR_ELG"))
    )
    (comp (ref "C304")
      (value "330u")
      (footprint "eagle-import:PANASONIC_G")
      (libsource (lib "eagle-import") (part "CAPACITOR_ELG"))
    )
    (comp (ref "C305")
      (value "4u7")
      (footprint "eagle-import:0603_WAVE")
      (libsource (lib "eagle-import") (part "MLCC0603"))
    )
    (comp (ref "C306")
      (value "330u")
      (footprint "eagle-import:PANASONIC_G")
      (libsource (lib "eagle-import") (part "CAPACITOR_ELG"))
    )
    (comp (ref "C307")
      (value "100u")
      (footprint "eagle-import:PANASONIC_D")
      (libsource (lib "eagle-import") (part "CAPACITOR_ELD"))
    )
    (comp (ref "C308")
      (value "330u")
      (footprint "eagle-import:PANASONIC_G")
      (libsource (lib "eagle-import") (part "CAPACITOR_ELG"))
    )
    (comp (ref "C309")
      (value "4u7")
      (footprint "eagle-import:0603_WAVE")
      (libsource (lib "eagle-import") (part "MLCC0603"))
    )
    (comp (ref "C310")
      (value "4u7")
      (footprint "eagle-import:0603_WAVE")
      (libsource (lib "eagle-import") (part "MLCC0603"))
    )
    (comp (ref "D301")
      (value "SK54L")
      (footprint "eagle-import:DO214AA")
      (libsource (lib "eagle-import") (part "SK54L"))
    )
    (comp (ref "D302")
      (value "LED0603")
      (footprint "eagle-import:CHIPLED_0603")
      (libsource (lib "eagle-import") (part "LED0603"))
    )
    (comp (ref "J301")
      (value "2P-6.35P")
      (footprint "eagle-import:2P-6.35P")
      (libsource (lib "eagle-import") (part "2P-6.35P"))
    )
    (comp (ref "J302")
      (value "2P-6.35P")
      (footprint "eagle-import:2P-6.35P")
      (libsource (lib "eagle-import") (part "2P-6.35P"))
    )
    (comp (ref "L301")
      (value "68uH")
      (footprint "eagle-import:CDRH104R")
      (libsource (lib "eagle-import") (part "INDUCTORCDRH104R"))
    )
    (comp (ref "P301")
      (value "POWPAD")
      (footprint "eagle-import:TH-HP")
      (libsource (lib "eagle-import") (part "POWPAD"))
    )
    (comp (ref "P302")
      (value "POWPAD")
      (footprint "eagle-import:TH-HP")
      (libsource (lib "eagle-import") (part "POWPAD"))
    )
    (comp (ref "R301")
      (value "10M")
      (footprint "eagle-import:0603_WAVE")
      (libsource (lib "eagle-import") (part "RESISTOR0603"))
    )
    (comp (ref "R302")
      (value "10k")
      (footprint "eagle-import:0603_WAVE")
      (libsource (lib "eagle-import") (part "RESISTOR0603"))
    )
    (comp (ref "R303")
      (value "4.2k")
      (footprint "eagle-import:0603_WAVE")
      (libsource (lib "eagle-import") (part "RESISTOR0603"))
    )
    (comp (ref "R304")
      (value "1.2k")
      (footprint "eagle-import:0603_WAVE")
      (libsource (lib "eagle-import") (part "RESISTOR0603"))
    )
    (comp (ref "R305")
      (value "2k")
      (footprint "eagle-import:0603_WAVE")
      (libsource (lib "eagle-import") (part "RESISTOR0603"))
    )
    (comp (ref "U301")
      (value "MIC4682")
      (footprint "eagle-import:SOIC8")
      (libsource (lib "eagle-import") (part "MIC4682"))
    )
    (comp (ref "U302")
      (value "MIC39101")
      (footprint "eagle-import:SOIC8")
      (libsource (lib "eagle-import") (part "MIC39101"))
    )
    (comp (ref "U303")
      (value "MIC39101")
      (footprint "eagle-import:SOIC8")
      (libsource (lib "eagle-import") (part "MIC39101"))
    )
    (comp (ref "C201")
      (value "4u7")
      (footprint "eagle-import:0603_WAVE")
      (libsource (lib "eagle-import") (part "MLCC0603"))
    )
    (comp (ref "C202")
      (value "4u7")
      (footprint "eagle-import:0603_WAVE")
      (libsource (lib "eagle-import") (part "MLCC0603"))
    )
    (comp (ref "C203")
      (value "4u7")
      (footprint "eagle-import:0603_WAVE")
      (libsource (lib "eagle-import") (part "MLCC0603"))
    )
    (comp (ref "C204")
      (value "4u7")
      (footprint "eagle-import:0603_WAVE")
      (libsource (lib "eagle-import") (part "MLCC0603"))
    )
    (comp (ref "C205")
      (value "4u7")
      (footprint "eagle-import:0603_WAVE")
      (libsource (lib "eagle-import") (part "MLCC0603"))
    )
    (comp (ref "C206")
      (value "100p")
      (footprint "eagle-import:0603_WAVE")
      (libsource (lib "eagle-import") (part "MLCC0603"))
    )
    (comp (ref "C207")
      (value "100p")
      (footprint "eagle-import:0603_WAVE")
      (libsource (lib "eagle-import") (part "MLCC0603"))
    )
    (comp (ref "C208")
      (value "100p")
      (footprint "eagle-import:0603_WAVE")
      (libsource (lib "eagle-import") (part "MLCC0603"))
    )
    (comp (ref "C209")
      (value "100p")
      (footprint "eagle-import:0603_WAVE")
      (libsource (lib "eagle-import") (part "MLCC0603"))
    )
    (comp (ref "C210")
      (value "100p")
      (footprint "eagle-import:0603_WAVE")
      (libsource (lib "eagle-import") (part "MLCC0603"))
    )
    (comp (ref "C211")
      (value "100p")
      (footprint "eagle-import:0603_WAVE")
      (libsource (lib "eagle-import") (part "MLCC0603"))
    )
    (comp (ref "C212")
      (value "100p")
      (footprint "eagle-import:0603_WAVE")
      (libsource (lib "eagle-import") (part "MLCC0603"))
    )
    (comp (ref "C213")
      (value "100p")
      (footprint "eagle-import:0603_WAVE")
      (libsource (lib "eagle-import") (part "MLCC0603"))
    )
    (comp (ref "C214")
      (value "100n")
      (footprint "eagle-import:0603_WAVE")
      (libsource (lib "eagle-import") (part "MLCC0603"))
    )
    (comp (ref "C215")
      (value "100n")
      (footprint "eagle-import:0603_WAVE")
      (libsource (lib "eagle-import") (part "MLCC0603"))
    )
    (comp (ref "C216")
      (value "100n")
      (footprint "eagle-import:0603_WAVE")
      (libsource (lib "eagle-import") (part "MLCC0603"))
    )
    (comp (ref "C217")
      (value "100n")
      (footprint "eagle-import:0603_WAVE")
      (libsource (lib "eagle-import") (part "MLCC0603"))
    )
    (comp (ref "C218")
      (value "100p")
      (footprint "eagle-import:0603_WAVE")
      (libsource (lib "eagle-import") (part "MLCC0603"))
    )
    (comp (ref "C219")
      (value "100p")
      (footprint "eagle-import:0603_WAVE")
      (libsource (lib "eagle-import") (part "MLCC0603"))
    )
    (comp (ref "C220")
      (value "100p")
      (footprint "eagle-import:0603_WAVE")
      (libsource (lib "eagle-import") (part "MLCC0603"))
    )
    (comp (ref "C221")
      (value "100p")
      (footprint "eagle-import:0603_WAVE")
      (libsource (lib "eagle-import") (part "MLCC0603"))
    )
    (comp (ref "C222")
      (value "100n")
      (footprint "eagle-import:0603_WAVE")
      (libsource (lib "eagle-import") (part "MLCC0603"))
    )
    (comp (ref "C223")
      (value "100n")
      (footprint "eagle-import:0603_WAVE")
      (libsource (lib "eagle-import") (part "MLCC0603"))
    )
    (comp (ref "C224")
      (value "100n")
      (footprint "eagle-import:0603_WAVE")
      (libsource (lib "eagle-import") (part "MLCC0603"))
    )
    (comp (ref "C225")
      (value "100n")
      (footprint "eagle-import:0603_WAVE")
      (libsource (lib "eagle-import") (part "MLCC0603"))
    )
    (comp (ref "C226")
      (value "100p")
      (footprint "eagle-import:0603_WAVE")
      (libsource (lib "eagle-import") (part "MLCC0603"))
    )
    (comp (ref "C227")
      (value "100p")
      (footprint "eagle-import:0603_WAVE")
      (libsource (lib "eagle-import") (part "MLCC0603"))
    )
    (comp (ref "C228")
      (value "100p")
      (footprint "eagle-import:0603_WAVE")
      (libsource (lib "eagle-import") (part "MLCC0603"))
    )
    (comp (ref "D201")
      (value "BAT54S")
      (footprint "eagle-import:SOT-23-3")
      (libsource (lib "eagle-import") (part "BAT54S"))
    )
    (comp (ref "D202")
      (value "BAT54S")
      (footprint "eagle-import:SOT-23-3")
      (libsource (lib "eagle-import") (part "BAT54S"))
    )
    (comp (ref "D203")
      (value "BAT54S")
      (footprint "eagle-import:SOT-23-3")
      (libsource (lib "eagle-import") (part "BAT54S"))
    )
    (comp (ref "J201")
      (value "SH-5")
      (footprint "eagle-import:SM05B-SSR-H-TB")
      (libsource (lib "eagle-import") (part "SH-5"))
    )
    (comp (ref "J202")
      (value "SH-5")
      (footprint "eagle-import:SM05B-SSR-H-TB")
      (libsource (lib "eagle-import") (part "SH-5"))
    )
    (comp (ref "J203")
      (value "SH-5")
      (footprint "eagle-import:SM05B-SSR-H-TB")
      (libsource (lib "eagle-import") (part "SH-5"))
    )
    (comp (ref "J204")
      (value "SH-5")
      (footprint "eagle-import:SM05B-SSR-H-TB")
      (libsource (lib "eagle-import") (part "SH-5"))
    )
    (comp (ref "J205")
      (value "SH-5")
      (footprint "eagle-import:SM05B-SSR-H-TB")
      (libsource (lib "eagle-import") (part "SH-5"))
    )
    (comp (ref "R201")
      (value "100")
      (footprint "eagle-import:0603_WAVE")
      (libsource (lib "eagle-import") (part "RESISTOR0603"))
    )
    (comp (ref "R202")
      (value "100")
      (footprint "eagle-import:0603_WAVE")
      (libsource (lib "eagle-import") (part "RESISTOR0603"))
    )
    (comp (ref "R203")
      (value "100")
      (footprint "eagle-import:0603_WAVE")
      (libsource (lib "eagle-import") (part "RESISTOR0603"))
    )
    (comp (ref "R204")
      (value "100")
      (footprint "eagle-import:0603_WAVE")
      (libsource (lib "eagle-import") (part "RESISTOR0603"))
    )
    (comp (ref "R205")
      (value "100")
      (footprint "eagle-import:0603_WAVE")
      (libsource (lib "eagle-import") (part "RESISTOR0603"))
    )
    (comp (ref "R206")
      (value "100")
      (footprint "eagle-import:0603_WAVE")
      (libsource (lib "eagle-import") (part "RESISTOR0603"))
    )
    (comp (ref "R207")
      (value "100")
      (footprint "eagle-import:0603_WAVE")
      (libsource (lib "eagle-import") (part "RESISTOR0603"))
    )
    (comp (ref "R208")
      (value "100")
      (footprint "eagle-import:0603_WAVE")
      (libsource (lib "eagle-import") (part "RESISTOR0603"))
    )
    (comp (ref "R209")
      (value "100")
      (footprint "eagle-import:0603_WAVE")
      (libsource (lib "eagle-import") (part "RESISTOR0603"))
    )
    (comp (ref "R210")
      (value "100")
      (footprint "eagle-import:0603_WAVE")
      (libsource (lib "eagle-import") (part "RESISTOR0603"))
    )
    (comp (ref "R211")
      (value "100")
      (footprint "eagle-import:0603_WAVE")
      (libsource (lib "eagle-import") (part "RESISTOR0603"))
    )
    (comp (ref "R212")
      (value "100")
      (footprint "eagle-import:0603_WAVE")
      (libsource (lib "eagle-import") (part "RESISTOR0603"))
    )
    (comp (ref "R213")
      (value "100")
      (footprint "eagle-import:0603_WAVE")
      (libsource (lib "eagle-import") (part "RESISTOR0603"))
    )
    (comp (ref "R214")
      (value "100k")
      (footprint "eagle-import:0603_WAVE")
      (libsource (lib "eagle-import") (part "RESISTOR0603"))
    )
    (comp (ref "R215")
      (value "100k")
      (footprint "eagle-import:0603_WAVE")
      (libsource (lib "eagle-import") (part "RESISTOR0603"))
    )
    (comp (ref "R216")
      (value "100k")
      (footprint "eagle-import:0603_WAVE")
      (libsource (lib "eagle-import") (part "RESISTOR0603"))
    )
    (comp (ref "R217")
      (value "100k")
      (footprint "eagle-import:0603_WAVE")
      (libsource (lib "eagle-import") (part "RESISTOR0603"))
    )
    (comp (ref "R218")
      (value "100")
      (footprint "eagle-import:0603_WAVE")
      (libsource (lib "eagle-import") (part "RESISTOR0603"))
    )
    (comp (ref "R219")
      (value "100k")
      (footprint "eagle-import:0603_WAVE")
      (libsource (lib "eagle-import") (part "RESISTOR0603"))
    )
    (comp (ref "R220")
      (value "100k")
      (footprint "eagle-import:0603_WAVE")
      (libsource (lib "eagle-import") (part "RESISTOR0603"))
    )
    (comp (ref "R221")
      (value "100k")
      (footprint "eagle-import:0603_WAVE")
      (libsource (lib "eagle-import") (part "RESISTOR0603"))
    )
    (comp (ref "R222")
      (value "100k")
      (footprint "eagle-import:0603_WAVE")
      (libsource (lib "eagle-import") (part "RESISTOR0603"))
    )
    (comp (ref "R223")
      (value "100k")
      (footprint "eagle-import:0603_WAVE")
      (libsource (lib "eagle-import") (part "RESISTOR0603"))
    )
    (comp (ref "R224")
      (value "100k")
      (footprint "eagle-import:0603_WAVE")
      (libsource (lib "eagle-import") (part "RESISTOR0603"))
    )
    (comp (ref "R225")
      (value "100k")
      (footprint "eagle-import:0603_WAVE")
      (libsource (lib "eagle-import") (part "RESISTOR0603"))
    )
    (comp (ref "R226")
      (value "100k")
      (footprint "eagle-import:0603_WAVE")
      (libsource (lib "eagle-import") (part "RESISTOR0603"))
    )
    (comp (ref "R227")
      (value "100")
      (footprint "eagle-import:0603_WAVE")
      (libsource (lib "eagle-import") (part "RESISTOR0603"))
    )
    (comp (ref "U201")
      (value "SRV05-4")
      (footprint "eagle-import:SOT23-6")
      (libsource (lib "eagle-import") (part "SRV05-4"))
    )
    (comp (ref "U202")
      (value "SRV05-4")
      (footprint "eagle-import:SOT23-6")
      (libsource (lib "eagle-import") (part "SRV05-4"))
    )
    (comp (ref "U203")
      (value "SRV05-4")
      (footprint "eagle-import:SOT23-6")
      (libsource (lib "eagle-import") (part "SRV05-4"))
    )
    (comp (ref "U204")
      (value "SRV05-4")
      (footprint "eagle-import:SOT23-6")
      (libsource (lib "eagle-import") (part "SRV05-4"))
    )
    (comp (ref "U205")
      (value "74LVC3G17")
      (footprint "eagle-import:TSSOP-8")
      (libsource (lib "eagle-import") (part "74LVC3G17"))
    )
    (comp (ref "U206")
      (value "74LVC3G17")
      (footprint "eagle-import:TSSOP-8")
      (libsource (lib "eagle-import") (part "74LVC3G17"))
    )
    (comp (ref "U207")
      (value "74LVC3G17")
      (footprint "eagle-import:TSSOP-8")
      (libsource (lib "eagle-import") (part "74LVC3G17"))
    )
    (comp (ref "U208")
      (value "74LVC3G17")
      (footprint "eagle-import:TSSOP-8")
      (libsource (lib "eagle-import") (part "74LVC3G17"))
    )
  )
  (nets
    (net (code "1") (name "1.8V") (class "Default")
      (node (ref "C103") (pin "P$1") (pinfunction "P$1_P$1") (pintype "bidirectional"))
      (node (ref "C105") (pin "P$1") (pinfunction "P$1_P$1") (pintype "bidirectional"))
      (node (ref "C107") (pin "P$1") (pinfunction "P$1_P$1") (pintype "bidirectional"))
      (node (ref "U102") (pin "15") (pinfunction "VCC_CORE_15") (pintype "bidirectional"))
      (node (ref "U102") (pin "45") (pinfunction "VCC_CORE_45") (pintype "bidirectional"))
      (node (ref "U102") (pin "63") (pinfunction "VCC_CORE_63") (pintype "bidirectional"))
    )
    (net (code "2") (name "3.3V") (class "Default")
      (node (ref "C101") (pin "P$1") (pinfunction "P$1_P$1") (pintype "bidirectional"))
      (node (ref "C102") (pin "P$1") (pinfunction "P$1_P$1") (pintype "bidirectional"))
      (node (ref "C104") (pin "P$1") (pinfunction "P$1_P$1") (pintype "bidirectional"))
      (node (ref "C106") (pin "P$1") (pinfunction "P$1_P$1") (pintype "bidirectional"))
      (node (ref "C108") (pin "P$1") (pinfunction "P$1_P$1") (pintype "bidirectional"))
      (node (ref "C109") (pin "P$1") (pinfunction "P$1_P$1") (pintype "bidirectional"))
      (node (ref "C110") (pin "P$1") (pinfunction "P$1_P$1") (pintype "bidirectional"))
      (node (ref "C111") (pin "P$1") (pinfunction "P$1_P$1") (pintype "bidirectional"))
      (node (ref "C214") (pin "P$1") (pinfunction "P$1_P$1") (pintype "bidirectional"))
      (node (ref "C215") (pin "P$1") (pinfunction "P$1_P$1") (pintype "bidirectional"))
      (node (ref "C216") (pin "P$1") (pinfunction "P$1_P$1") (pintype "bidirectional"))
      (node (ref "C217") (pin "P$1") (pinfunction "P$1_P$1") (pintype "bidirectional"))
      (node (ref "C309") (pin "P$1") (pinfunction "P$1_P$1") (pintype "bidirectional"))
      (node (ref "C405") (pin "P$1") (pinfunction "P$1_P$1") (pintype "bidirectional"))
      (node (ref "C407") (pin "P$1") (pinfunction "P$1_P$1") (pintype "bidirectional"))
      (node (ref "C409") (pin "P$1") (pinfunction "P$1_P$1") (pintype "bidirectional"))
      (node (ref "C411") (pin "P$1") (pinfunction "P$1_P$1") (pintype "bidirectional"))
      (node (ref "C413") (pin "P$1") (pinfunction "P$1_P$1") (pintype "bidirectional"))
      (node (ref "C414") (pin "P$1") (pinfunction "P$1_P$1") (pintype "bidirectional"))
      (node (ref "C415") (pin "P$1") (pinfunction "P$1_P$1") (pintype "bidirectional"))
      (node (ref "C416") (pin "P$1") (pinfunction "P$1_P$1") (pintype "bidirectional"))
      (node (ref "C501") (pin "P$1") (pinfunction "P$1_P$1") (pintype "bidirectional"))
      (node (ref "C502") (pin "P$1") (pinfunction "P$1_P$1") (pintype "bidirectional"))
      (node (ref "D504") (pin "P$2") (pinfunction "2_P$2") (pintype "bidirectional"))
      (node (ref "D505") (pin "P$2") (pinfunction "2_P$2") (pintype "bidirectional"))
      (node (ref "D506") (pin "P$2") (pinfunction "2_P$2") (pintype "bidirectional"))
      (node (ref "J505") (pin "1") (pinfunction "S_1") (pintype "passive"))
      (node (ref "R101") (pin "P$2") (pinfunction "P$2_P$2") (pintype "bidirectional"))
      (node (ref "R102") (pin "P$1") (pinfunction "P$1_P$1") (pintype "bidirectional"))
      (node (ref "R501") (pin "P$1") (pinfunction "P$1_P$1") (pintype "bidirectional"))
      (node (ref "R502") (pin "P$2") (pinfunction "P$2_P$2") (pintype "bidirectional"))
      (node (ref "R503") (pin "P$2") (pinfunction "P$2_P$2") (pintype "bidirectional"))
      (node (ref "U101") (pin "6") (pinfunction "VDD_6") (pintype "bidirectional"))
      (node (ref "U102") (pin "13") (pinfunction "VCC_13") (pintype "bidirectional"))
      (node (ref "U102") (pin "2") (pinfunction "VCC_2") (pintype "bidirectional"))
      (node (ref "U102") (pin "43") (pinfunction "VCC_43") (pintype "bidirectional"))
      (node (ref "U102") (pin "52") (pinfunction "PLL_VCC_52") (pintype "bidirectional"))
      (node (ref "U102") (pin "61") (pinfunction "VCC_61") (pintype "bidirectional"))
      (node (ref "U102") (pin "72") (pinfunction "VCC_72") (pintype "bidirectional"))
      (node (ref "U205") (pin "8") (pinfunction "VCC_8") (pintype "bidirectional"))
      (node (ref "U206") (pin "8") (pinfunction "VCC_8") (pintype "bidirectional"))
      (node (ref "U207") (pin "8") (pinfunction "VCC_8") (pintype "bidirectional"))
      (node (ref "U208") (pin "8") (pinfunction "VCC_8") (pintype "bidirectional"))
      (node (ref "U302") (pin "3") (pinfunction "VOUT_3") (pintype "bidirectional"))
      (node (ref "U401") (pin "3") (pinfunction "VDDI_3") (pintype "bidirectional"))
      (node (ref "U401") (pin "8") (pinfunction "VDDI_8") (pintype "bidirectional"))
      (node (ref "U402") (pin "3") (pinfunction "VDDI_3") (pintype "bidirectional"))
      (node (ref "U402") (pin "8") (pinfunction "VDDI_8") (pintype "bidirectional"))
      (node (ref "U403") (pin "3") (pinfunction "VDDI_3") (pintype "bidirectional"))
      (node (ref "U403") (pin "8") (pinfunction "VDDI_8") (pintype "bidirectional"))
      (node (ref "U404") (pin "3") (pinfunction "VDDI_3") (pintype "bidirectional"))
      (node (ref "U404") (pin "8") (pinfunction "VDDI_8") (pintype "bidirectional"))
      (node (ref "U501") (pin "5") (pinfunction "VIO_5") (pintype "bidirectional"))
      (node (ref "U501") (pin "6") (pinfunction "VDD_6") (pintype "bidirectional"))
      (node (ref "U501") (pin "7") (pinfunction "VREGIN_7") (pintype "bidirectional"))
    )
    (net (code "3") (name "5V") (class "Default")
      (node (ref "C112") (pin "P$1") (pinfunction "P$1_P$1") (pintype "bidirectional"))
      (node (ref "C113") (pin "P$1") (pinfunction "P$1_P$1") (pintype "bidirectional"))
      (node (ref "C201") (pin "P$1") (pinfunction "P$1_P$1") (pintype "bidirectional"))
      (node (ref "C202") (pin "P$1") (pinfunction "P$1_P$1") (pintype "bidirectional"))
      (node (ref "C203") (pin "P$1") (pinfunction "P$1_P$1") (pintype "bidirectional"))
      (node (ref "C204") (pin "P$1") (pinfunction "P$1_P$1") (pintype "bidirectional"))
      (node (ref "C205") (pin "P$1") (pinfunction "P$1_P$1") (pintype "bidirectional"))
      (node (ref "C222") (pin "P$1") (pinfunction "P$1_P$1") (pintype "bidirectional"))
      (node (ref "C223") (pin "P$1") (pinfunction "P$1_P$1") (pintype "bidirectional"))
      (node (ref "C224") (pin "P$1") (pinfunction "P$1_P$1") (pintype "bidirectional"))
      (node (ref "C225") (pin "P$1") (pinfunction "P$1_P$1") (pintype "bidirectional"))
      (node (ref "C310") (pin "P$1") (pinfunction "P$1_P$1") (pintype "bidirectional"))
      (node (ref "C422") (pin "P$1") (pinfunction "P$1_P$1") (pintype "bidirectional"))
      (node (ref "C423") (pin "P$1") (pinfunction "P$1_P$1") (pintype "bidirectional"))
      (node (ref "D101") (pin "P$2") (pinfunction "2_P$2") (pintype "bidirectional"))
      (node (ref "D201") (pin "P$2") (pinfunction "2_P$2") (pintype "bidirectional"))
      (node (ref "D202") (pin "P$2") (pinfunction "2_P$2") (pintype "bidirectional"))
      (node (ref "D203") (pin "P$2") (pinfunction "2_P$2") (pintype "bidirectional"))
      (node (ref "J201") (pin "1") (pinfunction "S_1") (pintype "passive"))
      (node (ref "J202") (pin "1") (pinfunction "S_1") (pintype "passive"))
      (node (ref "J203") (pin "1") (pinfunction "S_1") (pintype "passive"))
      (node (ref "J204") (pin "1") (pinfunction "S_1") (pintype "passive"))
      (node (ref "J205") (pin "1") (pinfunction "S_1") (pintype "passive"))
      (node (ref "J402") (pin "1") (pinfunction "S_1") (pintype "passive"))
      (node (ref "R103") (pin "P$2") (pinfunction "P$2_P$2") (pintype "bidirectional"))
      (node (ref "R106") (pin "P$2") (pinfunction "P$2_P$2") (pintype "bidirectional"))
      (node (ref "R109") (pin "P$2") (pinfunction "P$2_P$2") (pintype "bidirectional"))
      (node (ref "R117") (pin "P$2") (pinfunction "P$2_P$2") (pintype "bidirectional"))
      (node (ref "R120") (pin "P$2") (pinfunction "P$2_P$2") (pintype "bidirectional"))
      (node (ref "R214") (pin "P$1") (pinfunction "P$1_P$1") (pintype "bidirectional"))
      (node (ref "R215") (pin "P$1") (pinfunction "P$1_P$1") (pintype "bidirectional"))
      (node (ref "R216") (pin "P$1") (pinfunction "P$1_P$1") (pintype "bidirectional"))
      (node (ref "R217") (pin "P$1") (pinfunction "P$1_P$1") (pintype "bidirectional"))
      (node (ref "R219") (pin "P$1") (pinfunction "P$1_P$1") (pintype "bidirectional"))
      (node (ref "R220") (pin "P$1") (pinfunction "P$1_P$1") (pintype "bidirectional"))
      (node (ref "R221") (pin "P$1") (pinfunction "P$1_P$1") (pintype "bidirectional"))
      (node (ref "R222") (pin "P$1") (pinfunction "P$1_P$1") (pintype "bidirectional"))
      (node (ref "R223") (pin "P$1") (pinfunction "P$1_P$1") (pintype "bidirectional"))
      (node (ref "R224") (pin "P$1") (pinfunction "P$1_P$1") (pintype "bidirectional"))
      (node (ref "R225") (pin "P$1") (pinfunction "P$1_P$1") (pintype "bidirectional"))
      (node (ref "R226") (pin "P$1") (pinfunction "P$1_P$1") (pintype "bidirectional"))
      (node (ref "R427") (pin "P$2") (pinfunction "P$2_P$2") (pintype "bidirectional"))
      (node (ref "U102") (pin "23") (pinfunction "V5_23") (pintype "bidirectional"))
      (node (ref "U201") (pin "5") (pinfunction "VCC_5") (pintype "bidirectional"))
      (node (ref "U202") (pin "5") (pinfunction "VCC_5") (pintype "bidirectional"))
      (node (ref "U203") (pin "5") (pinfunction "VCC_5") (pintype "bidirectional"))
      (node (ref "U204") (pin "5") (pinfunction "VCC_5") (pintype "bidirectional"))
      (node (ref "U303") (pin "3") (pinfunction "VOUT_3") (pintype "bidirectional"))
      (node (ref "U405") (pin "6") (pinfunction "P$1_6") (pintype "bidirectional"))
      (node (ref "U405") (pin "7") (pinfunction "P$1_7") (pintype "bidirectional"))
      (node (ref "U406") (pin "6") (pinfunction "P$1_6") (pintype "bidirectional"))
      (node (ref "U406") (pin "7") (pinfunction "P$1_7") (pintype "bidirectional"))
    )
    (net (code "4") (name "12V") (class "Default")
      (node (ref "C301") (pin "P$1") (pinfunction "P$1_P$1") (pintype "bidirectional"))
      (node (ref "C302") (pin "+") (pinfunction "AN_+") (pintype "bidirectional"))
      (node (ref "C401") (pin "P$1") (pinfunction "P$1_P$1") (pintype "bidirectional"))
      (node (ref "C402") (pin "P$1") (pinfunction "P$1_P$1") (pintype "bidirectional"))
      (node (ref "C403") (pin "P$1") (pinfunction "P$1_P$1") (pintype "bidirectional"))
      (node (ref "C404") (pin "P$1") (pinfunction "P$1_P$1") (pintype "bidirectional"))
      (node (ref "C406") (pin "P$1") (pinfunction "P$1_P$1") (pintype "bidirectional"))
      (node (ref "C408") (pin "P$1") (pinfunction "P$1_P$1") (pintype "bidirectional"))
      (node (ref "C410") (pin "P$1") (pinfunction "P$1_P$1") (pintype "bidirectional"))
      (node (ref "C412") (pin "P$1") (pinfunction "P$1_P$1") (pintype "bidirectional"))
      (node (ref "C421") (pin "P$1") (pinfunction "P$1_P$1") (pintype "bidirectional"))
      (node (ref "C424") (pin "P$1") (pinfunction "P$1_P$1") (pintype "bidirectional"))
      (node (ref "J301") (pin "2") (pinfunction "S_2") (pintype "passive"))
      (node (ref "R301") (pin "P$2") (pinfunction "P$2_P$2") (pintype "bidirectional"))
      (node (ref "R409") (pin "P$1") (pinfunction "P$1_P$1") (pintype "bidirectional"))
      (node (ref "R410") (pin "P$1") (pinfunction "P$1_P$1") (pintype "bidirectional"))
      (node (ref "R411") (pin "P$1") (pinfunction "P$1_P$1") (pintype "bidirectional"))
      (node (ref "R412") (pin "P$1") (pinfunction "P$1_P$1") (pintype "bidirectional"))
      (node (ref "U301") (pin "5") (pinfunction "IN_5") (pintype "bidirectional"))
      (node (ref "U401") (pin "11") (pinfunction "VDDB_11") (pintype "bidirectional"))
      (node (ref "U402") (pin "11") (pinfunction "VDDB_11") (pintype "bidirectional"))
      (node (ref "U403") (pin "11") (pinfunction "VDDB_11") (pintype "bidirectional"))
      (node (ref "U404") (pin "11") (pinfunction "VDDB_11") (pintype "bidirectional"))
      (node (ref "U407") (pin "8") (pinfunction "VDD_8") (pintype "bidirectional"))
    )
    (net (code "5") (name "ADC_I0_U_PF") (class "Default")
      (node (ref "R113") (pin "P$2") (pinfunction "P$2_P$2") (pintype "bidirectional"))
      (node (ref "U405") (pin "5") (pinfunction "O_5") (pintype "bidirectional"))
    )
    (net (code "6") (name "ADC_I1_V_PF") (class "Default")
      (node (ref "R115") (pin "P$2") (pinfunction "P$2_P$2") (pintype "bidirectional"))
      (node (ref "U406") (pin "5") (pinfunction "O_5") (pintype "bidirectional"))
    )
    (net (code "7") (name "ADC_T_MOSFETS") (class "Default")
      (node (ref "C425") (pin "P$1") (pinfunction "P$1_P$1") (pintype "bidirectional"))
      (node (ref "R111") (pin "P$2") (pinfunction "P$2_P$2") (pintype "bidirectional"))
      (node (ref "R427") (pin "P$1") (pinfunction "P$1_P$1") (pintype "bidirectional"))
      (node (ref "R428") (pin "P$2") (pinfunction "P$2_P$2") (pintype "bidirectional"))
    )
    (net (code "8") (name "ADC_T_MOTOR") (class "Default")
      (node (ref "C432") (pin "P$1") (pinfunction "P$1_P$1") (pintype "bidirectional"))
      (node (ref "J402") (pin "2") (pinfunction "S_2") (pintype "passive"))
      (node (ref "R112") (pin "P$1") (pinfunction "P$1_P$1") (pintype "bidirectional"))
      (node (ref "R430") (pin "P$2") (pinfunction "P$2_P$2") (pintype "bidirectional"))
    )
    (net (code "9") (name "AENC_UX_P") (class "Default")
      (node (ref "C226") (pin "P$1") (pinfunction "P$1_P$1") (pintype "bidirectional"))
      (node (ref "D201") (pin "P$3") (pinfunction "3_P$3") (pintype "bidirectional"))
      (node (ref "R213") (pin "P$2") (pinfunction "P$2_P$2") (pintype "bidirectional"))
      (node (ref "U102") (pin "25") (pinfunction "AENC_UX_POS_25") (pintype "bidirectional"))
    )
    (net (code "10") (name "AENC_VN_P") (class "Default")
      (node (ref "C227") (pin "P$1") (pinfunction "P$1_P$1") (pintype "bidirectional"))
      (node (ref "D202") (pin "P$3") (pinfunction "3_P$3") (pintype "bidirectional"))
      (node (ref "R218") (pin "P$2") (pinfunction "P$2_P$2") (pintype "bidirectional"))
      (node (ref "U102") (pin "27") (pinfunction "AENC_VN_POS_27") (pintype "bidirectional"))
    )
    (net (code "11") (name "AENC_WY_P") (class "Default")
      (node (ref "C228") (pin "P$1") (pinfunction "P$1_P$1") (pintype "bidirectional"))
      (node (ref "D203") (pin "P$3") (pinfunction "3_P$3") (pintype "bidirectional"))
      (node (ref "R227") (pin "P$2") (pinfunction "P$2_P$2") (pintype "bidirectional"))
      (node (ref "U102") (pin "29") (pinfunction "AENC_WY_POS_29") (pintype "bidirectional"))
    )
    (net (code "12") (name "BRAKE") (class "Default")
      (node (ref "R429") (pin "P$2") (pinfunction "P$2_P$2") (pintype "bidirectional"))
      (node (ref "U102") (pin "31") (pinfunction "BRAKE_31") (pintype "bidirectional"))
    )
    (net (code "13") (name "CP2102_RX") (class "Default")
      (node (ref "J502") (pin "2") (pinfunction "S_2") (pintype "passive"))
      (node (ref "JP505") (pin "2") (pinfunction "2_2") (pintype "passive"))
      (node (ref "U102") (pin "11") (pinfunction "TXD_SYNCO_11") (pintype "bidirectional"))
    )
    (net (code "14") (name "CP2102_TX") (class "Default")
      (node (ref "J502") (pin "1") (pinfunction "S_1") (pintype "passive"))
      (node (ref "JP506") (pin "2") (pinfunction "2_2") (pintype "passive"))
      (node (ref "U102") (pin "10") (pinfunction "RXD_SYNCI_10") (pintype "bidirectional"))
    )
    (net (code "15") (name "D+") (class "Default")
      (node (ref "D503") (pin "3") (pinfunction "3_3") (pintype "bidirectional"))
      (node (ref "J503") (pin "D+") (pinfunction "D+_D+") (pintype "bidirectional"))
      (node (ref "U501") (pin "3") (pinfunction "D+_3") (pintype "bidirectional"))
    )
    (net (code "16") (name "D-") (class "Default")
      (node (ref "D503") (pin "2") (pinfunction "2_2") (pintype "bidirectional"))
      (node (ref "J503") (pin "D-") (pinfunction "D-_D-") (pintype "bidirectional"))
      (node (ref "U501") (pin "4") (pinfunction "D-_4") (pintype "bidirectional"))
    )
    (net (code "17") (name "DBG_SPI_MISO") (class "Default")
      (node (ref "J505") (pin "9") (pinfunction "S_9") (pintype "passive"))
      (node (ref "U102") (pin "4") (pinfunction "GPIO6_4") (pintype "bidirectional"))
    )
    (net (code "18") (name "DBG_SPI_MOSI") (class "Default")
      (node (ref "J505") (pin "7") (pinfunction "S_7") (pintype "passive"))
      (node (ref "U102") (pin "1") (pinfunction "GPIO5_1") (pintype "bidirectional"))
    )
    (net (code "19") (name "DBG_SPI_NSCS") (class "Default")
      (node (ref "J505") (pin "3") (pinfunction "S_3") (pintype "passive"))
      (node (ref "U102") (pin "75") (pinfunction "GPIO3_75") (pintype "bidirectional"))
    )
    (net (code "20") (name "DBG_SPI_SCK") (class "Default")
      (node (ref "J505") (pin "5") (pinfunction "S_5") (pintype "passive"))
      (node (ref "U102") (pin "76") (pinfunction "GPIO4_76") (pintype "bidirectional"))
    )
    (net (code "21") (name "DBG_SPI_TRG") (class "Default")
      (node (ref "J505") (pin "4") (pinfunction "S_4") (pintype "passive"))
      (node (ref "U102") (pin "5") (pinfunction "GPIO7_5") (pintype "bidirectional"))
    )
    (net (code "22") (name "DCBUS") (class "Default")
      (node (ref "C303") (pin "+") (pinfunction "AN_+") (pintype "bidirectional"))
      (node (ref "C304") (pin "+") (pinfunction "AN_+") (pintype "bidirectional"))
      (node (ref "C306") (pin "+") (pinfunction "AN_+") (pintype "bidirectional"))
      (node (ref "C308") (pin "+") (pinfunction "AN_+") (pintype "bidirectional"))
      (node (ref "J302") (pin "1") (pinfunction "S_1") (pintype "passive"))
      (node (ref "J403") (pin "1") (pinfunction "S_1") (pintype "passive"))
      (node (ref "P301") (pin "H1") (pinfunction "S_H1") (pintype "passive"))
      (node (ref "P301") (pin "H10") (pinfunction "S_H10") (pintype "passive"))
      (node (ref "P301") (pin "H11") (pinfunction "S_H11") (pintype "passive"))
      (node (ref "P301") (pin "H12") (pinfunction "S_H12") (pintype "passive"))
      (node (ref "P301") (pin "H2") (pinfunction "S_H2") (pintype "passive"))
      (node (ref "P301") (pin "H3") (pinfunction "S_H3") (pintype "passive"))
      (node (ref "P301") (pin "H4") (pinfunction "S_H4") (pintype "passive"))
      (node (ref "P301") (pin "H5") (pinfunction "S_H5") (pintype "passive"))
      (node (ref "P301") (pin "H6") (pinfunction "S_H6") (pintype "passive"))
      (node (ref "P301") (pin "H7") (pinfunction "S_H7") (pintype "passive"))
      (node (ref "P301") (pin "H8") (pinfunction "S_H8") (pintype "passive"))
      (node (ref "P301") (pin "H9") (pinfunction "S_H9") (pintype "passive"))
      (node (ref "P301") (pin "PAD") (pinfunction "S_PAD") (pintype "passive"))
      (node (ref "P405") (pin "H1") (pinfunction "S_H1") (pintype "passive"))
      (node (ref "P405") (pin "H10") (pinfunction "S_H10") (pintype "passive"))
      (node (ref "P405") (pin "H11") (pinfunction "S_H11") (pintype "passive"))
      (node (ref "P405") (pin "H12") (pinfunction "S_H12") (pintype "passive"))
      (node (ref "P405") (pin "H2") (pinfunction "S_H2") (pintype "passive"))
      (node (ref "P405") (pin "H3") (pinfunction "S_H3") (pintype "passive"))
      (node (ref "P405") (pin "H4") (pinfunction "S_H4") (pintype "passive"))
      (node (ref "P405") (pin "H5") (pinfunction "S_H5") (pintype "passive"))
      (node (ref "P405") (pin "H6") (pinfunction "S_H6") (pintype "passive"))
      (node (ref "P405") (pin "H7") (pinfunction "S_H7") (pintype "passive"))
      (node (ref "P405") (pin "H8") (pinfunction "S_H8") (pintype "passive"))
      (node (ref "P405") (pin "H9") (pinfunction "S_H9") (pintype "passive"))
      (node (ref "P405") (pin "PAD") (pinfunction "S_PAD") (pintype "passive"))
      (node (ref "Q401") (pin "D1") (pinfunction "D1_D1") (pintype "bidirectional"))
      (node (ref "Q401") (pin "D2") (pinfunction "D1_D2") (pintype "bidirectional"))
      (node (ref "Q401") (pin "D3") (pinfunction "D1_D3") (pintype "bidirectional"))
      (node (ref "Q401") (pin "D4") (pinfunction "D1_D4") (pintype "bidirectional"))
      (node (ref "Q402") (pin "D1") (pinfunction "D1_D1") (pintype "bidirectional"))
      (node (ref "Q402") (pin "D2") (pinfunction "D1_D2") (pintype "bidirectional"))
      (node (ref "Q402") (pin "D3") (pinfunction "D1_D3") (pintype "bidirectional"))
      (node (ref "Q402") (pin "D4") (pinfunction "D1_D4") (pintype "bidirectional"))
      (node (ref "Q403") (pin "D1") (pinfunction "D1_D1") (pintype "bidirectional"))
      (node (ref "Q403") (pin "D2") (pinfunction "D1_D2") (pintype "bidirectional"))
      (node (ref "Q403") (pin "D3") (pinfunction "D1_D3") (pintype "bidirectional"))
      (node (ref "Q403") (pin "D4") (pinfunction "D1_D4") (pintype "bidirectional"))
      (node (ref "Q404") (pin "D1") (pinfunction "D1_D1") (pintype "bidirectional"))
      (node (ref "Q404") (pin "D2") (pinfunction "D1_D2") (pintype "bidirectional"))
      (node (ref "Q404") (pin "D3") (pinfunction "D1_D3") (pintype "bidirectional"))
      (node (ref "Q404") (pin "D4") (pinfunction "D1_D4") (pintype "bidirectional"))
      (node (ref "R119") (pin "P$2") (pinfunction "P$2_P$2") (pintype "bidirectional"))
    )
    (net (code "23") (name "DIR") (class "Default")
      (node (ref "D505") (pin "P$3") (pinfunction "3_P$3") (pintype "bidirectional"))
      (node (ref "R508") (pin "P$2") (pinfunction "P$2_P$2") (pintype "bidirectional"))
      (node (ref "R511") (pin "P$2") (pinfunction "P$2_P$2") (pintype "bidirectional"))
      (node (ref "U102") (pin "56") (pinfunction "DIR_56") (pintype "bidirectional"))
    )
    (net (code "24") (name "ENC2_A") (class "Default")
      (node (ref "U102") (pin "64") (pinfunction "ENC2_A_64") (pintype "bidirectional"))
      (node (ref "U206") (pin "7") (pinfunction "Y_7") (pintype "output"))
    )
    (net (code "25") (name "ENC2_B") (class "Default")
      (node (ref "U102") (pin "65") (pinfunction "ENC2_B_65") (pintype "bidirectional"))
      (node (ref "U206") (pin "5") (pinfunction "Y_5") (pintype "output"))
    )
    (net (code "26") (name "ENC2_N") (class "Default")
      (node (ref "U102") (pin "66") (pinfunction "ENC2_N_66") (pintype "bidirectional"))
      (node (ref "U206") (pin "2") (pinfunction "Y_2") (pintype "output"))
    )
    (net (code "27") (name "ENC_A") (class "Default")
      (node (ref "U102") (pin "35") (pinfunction "ENC_A_35") (pintype "bidirectional"))
      (node (ref "U205") (pin "7") (pinfunction "Y_7") (pintype "output"))
    )
    (net (code "28") (name "ENC_B") (class "Default")
      (node (ref "U102") (pin "34") (pinfunction "ENC_B_34") (pintype "bidirectional"))
      (node (ref "U205") (pin "5") (pinfunction "Y_5") (pintype "output"))
    )
    (net (code "29") (name "ENC_N") (class "Default")
      (node (ref "U102") (pin "33") (pinfunction "ENC_N_33") (pintype "bidirectional"))
      (node (ref "U205") (pin "2") (pinfunction "Y_2") (pintype "output"))
    )
    (net (code "30") (name "ENO") (class "Default")
      (node (ref "R114") (pin "P$1") (pinfunction "P$1_P$1") (pintype "bidirectional"))
      (node (ref "U102") (pin "32") (pinfunction "ENO_32") (pintype "bidirectional"))
      (node (ref "U401") (pin "5") (pinfunction "EN_5") (pintype "bidirectional"))
      (node (ref "U402") (pin "5") (pinfunction "EN_5") (pintype "bidirectional"))
      (node (ref "U403") (pin "5") (pinfunction "EN_5") (pintype "bidirectional"))
      (node (ref "U404") (pin "5") (pinfunction "EN_5") (pintype "bidirectional"))
    )
    (net (code "31") (name "GND") (class "Default")
      (node (ref "C101") (pin "P$2") (pinfunction "P$2_P$2") (pintype "bidirectional"))
      (node (ref "C102") (pin "P$2") (pinfunction "P$2_P$2") (pintype "bidirectional"))
      (node (ref "C103") (pin "P$2") (pinfunction "P$2_P$2") (pintype "bidirectional"))
      (node (ref "C104") (pin "P$2") (pinfunction "P$2_P$2") (pintype "bidirectional"))
      (node (ref "C105") (pin "P$2") (pinfunction "P$2_P$2") (pintype "bidirectional"))
      (node (ref "C106") (pin "P$2") (pinfunction "P$2_P$2") (pintype "bidirectional"))
      (node (ref "C107") (pin "P$2") (pinfunction "P$2_P$2") (pintype "bidirectional"))
      (node (ref "C108") (pin "P$2") (pinfunction "P$2_P$2") (pintype "bidirectional"))
      (node (ref "C109") (pin "P$2") (pinfunction "P$2_P$2") (pintype "bidirectional"))
      (node (ref "C110") (pin "P$2") (pinfunction "P$2_P$2") (pintype "bidirectional"))
      (node (ref "C111") (pin "P$2") (pinfunction "P$2_P$2") (pintype "bidirectional"))
      (node (ref "C112") (pin "P$2") (pinfunction "P$2_P$2") (pintype "bidirectional"))
      (node (ref "C113") (pin "P$2") (pinfunction "P$2_P$2") (pintype "bidirectional"))
      (node (ref "C114") (pin "P$2") (pinfunction "P$2_P$2") (pintype "bidirectional"))
      (node (ref "C115") (pin "P$2") (pinfunction "P$2_P$2") (pintype "bidirectional"))
      (node (ref "C116") (pin "P$2") (pinfunction "P$2_P$2") (pintype "bidirectional"))
      (node (ref "C117") (pin "P$2") (pinfunction "P$2_P$2") (pintype "bidirectional"))
      (node (ref "C118") (pin "P$2") (pinfunction "P$2_P$2") (pintype "bidirectional"))
      (node (ref "C201") (pin "P$2") (pinfunction "P$2_P$2") (pintype "bidirectional"))
      (node (ref "C202") (pin "P$2") (pinfunction "P$2_P$2") (pintype "bidirectional"))
      (node (ref "C203") (pin "P$2") (pinfunction "P$2_P$2") (pintype "bidirectional"))
      (node (ref "C204") (pin "P$2") (pinfunction "P$2_P$2") (pintype "bidirectional"))
      (node (ref "C205") (pin "P$2") (pinfunction "P$2_P$2") (pintype "bidirectional"))
      (node (ref "C206") (pin "P$2") (pinfunction "P$2_P$2") (pintype "bidirectional"))
      (node (ref "C207") (pin "P$2") (pinfunction "P$2_P$2") (pintype "bidirectional"))
      (node (ref "C208") (pin "P$2") (pinfunction "P$2_P$2") (pintype "bidirectional"))
      (node (ref "C209") (pin "P$2") (pinfunction "P$2_P$2") (pintype "bidirectional"))
      (node (ref "C210") (pin "P$2") (pinfunction "P$2_P$2") (pintype "bidirectional"))
      (node (ref "C211") (pin "P$2") (pinfunction "P$2_P$2") (pintype "bidirectional"))
      (node (ref "C212") (pin "P$2") (pinfunction "P$2_P$2") (pintype "bidirectional"))
      (node (ref "C213") (pin "P$2") (pinfunction "P$2_P$2") (pintype "bidirectional"))
      (node (ref "C214") (pin "P$2") (pinfunction "P$2_P$2") (pintype "bidirectional"))
      (node (ref "C215") (pin "P$2") (pinfunction "P$2_P$2") (pintype "bidirectional"))
      (node (ref "C216") (pin "P$2") (pinfunction "P$2_P$2") (pintype "bidirectional"))
      (node (ref "C217") (pin "P$2") (pinfunction "P$2_P$2") (pintype "bidirectional"))
      (node (ref "C218") (pin "P$2") (pinfunction "P$2_P$2") (pintype "bidirectional"))
      (node (ref "C219") (pin "P$2") (pinfunction "P$2_P$2") (pintype "bidirectional"))
      (node (ref "C220") (pin "P$2") (pinfunction "P$2_P$2") (pintype "bidirectional"))
      (node (ref "C221") (pin "P$2") (pinfunction "P$2_P$2") (pintype "bidirectional"))
      (node (ref "C222") (pin "P$2") (pinfunction "P$2_P$2") (pintype "bidirectional"))
      (node (ref "C223") (pin "P$2") (pinfunction "P$2_P$2") (pintype "bidirectional"))
      (node (ref "C224") (pin "P$2") (pinfunction "P$2_P$2") (pintype "bidirectional"))
      (node (ref "C225") (pin "P$2") (pinfunction "P$2_P$2") (pintype "bidirectional"))
      (node (ref "C226") (pin "P$2") (pinfunction "P$2_P$2") (pintype "bidirectional"))
      (node (ref "C227") (pin "P$2") (pinfunction "P$2_P$2") (pintype "bidirectional"))
      (node (ref "C228") (pin "P$2") (pinfunction "P$2_P$2") (pintype "bidirectional"))
      (node (ref "C301") (pin "P$2") (pinfunction "P$2_P$2") (pintype "bidirectional"))
      (node (ref "C302") (pin "-") (pinfunction "CA_-") (pintype "bidirectional"))
      (node (ref "C303") (pin "-") (pinfunction "CA_-") (pintype "bidirectional"))
      (node (ref "C304") (pin "-") (pinfunction "CA_-") (pintype "bidirectional"))
      (node (ref "C305") (pin "P$2") (pinfunction "P$2_P$2") (pintype "bidirectional"))
      (node (ref "C306") (pin "-") (pinfunction "CA_-") (pintype "bidirectional"))
      (node (ref "C307") (pin "-") (pinfunction "CA_-") (pintype "bidirectional"))
      (node (ref "C308") (pin "-") (pinfunction "CA_-") (pintype "bidirectional"))
      (node (ref "C309") (pin "P$2") (pinfunction "P$2_P$2") (pintype "bidirectional"))
      (node (ref "C310") (pin "P$2") (pinfunction "P$2_P$2") (pintype "bidirectional"))
      (node (ref "C401") (pin "P$2") (pinfunction "P$2_P$2") (pintype "bidirectional"))
      (node (ref "C402") (pin "P$2") (pinfunction "P$2_P$2") (pintype "bidirectional"))
      (node (ref "C403") (pin "P$2") (pinfunction "P$2_P$2") (pintype "bidirectional"))
      (node (ref "C404") (pin "P$2") (pinfunction "P$2_P$2") (pintype "bidirectional"))
      (node (ref "C405") (pin "P$2") (pinfunction "P$2_P$2") (pintype "bidirectional"))
      (node (ref "C406") (pin "P$2") (pinfunction "P$2_P$2") (pintype "bidirectional"))
      (node (ref "C407") (pin "P$2") (pinfunction "P$2_P$2") (pintype "bidirectional"))
      (node (ref "C408") (pin "P$2") (pinfunction "P$2_P$2") (pintype "bidirectional"))
      (node (ref "C409") (pin "P$2") (pinfunction "P$2_P$2") (pintype "bidirectional"))
      (node (ref "C410") (pin "P$2") (pinfunction "P$2_P$2") (pintype "bidirectional"))
      (node (ref "C411") (pin "P$2") (pinfunction "P$2_P$2") (pintype "bidirectional"))
      (node (ref "C412") (pin "P$2") (pinfunction "P$2_P$2") (pintype "bidirectional"))
      (node (ref "C413") (pin "P$2") (pinfunction "P$2_P$2") (pintype "bidirectional"))
      (node (ref "C414") (pin "P$2") (pinfunction "P$2_P$2") (pintype "bidirectional"))
      (node (ref "C415") (pin "P$2") (pinfunction "P$2_P$2") (pintype "bidirectional"))
      (node (ref "C416") (pin "P$2") (pinfunction "P$2_P$2") (pintype "bidirectional"))
      (node (ref "C421") (pin "P$2") (pinfunction "P$2_P$2") (pintype "bidirectional"))
      (node (ref "C422") (pin "P$2") (pinfunction "P$2_P$2") (pintype "bidirectional"))
      (node (ref "C423") (pin "P$2") (pinfunction "P$2_P$2") (pintype "bidirectional"))
      (node (ref "C424") (pin "P$2") (pinfunction "P$2_P$2") (pintype "bidirectional"))
      (node (ref "C425") (pin "P$2") (pinfunction "P$2_P$2") (pintype "bidirectional"))
      (node (ref "C426") (pin "P$1") (pinfunction "P$1_P$1") (pintype "bidirectional"))
      (node (ref "C428") (pin "P$2") (pinfunction "P$2_P$2") (pintype "bidirectional"))
      (node (ref "C429") (pin "P$1") (pinfunction "P$1_P$1") (pintype "bidirectional"))
      (node (ref "C431") (pin "P$2") (pinfunction "P$2_P$2") (pintype "bidirectional"))
      (node (ref "C432") (pin "P$2") (pinfunction "P$2_P$2") (pintype "bidirectional"))
      (node (ref "C501") (pin "P$2") (pinfunction "P$2_P$2") (pintype "bidirectional"))
      (node (ref "C502") (pin "P$2") (pinfunction "P$2_P$2") (pintype "bidirectional"))
      (node (ref "C503") (pin "P$2") (pinfunction "P$2_P$2") (pintype "bidirectional"))
      (node (ref "D101") (pin "P$1") (pinfunction "1_P$1") (pintype "bidirectional"))
      (node (ref "D201") (pin "P$1") (pinfunction "1_P$1") (pintype "bidirectional"))
      (node (ref "D202") (pin "P$1") (pinfunction "1_P$1") (pintype "bidirectional"))
      (node (ref "D203") (pin "P$1") (pinfunction "1_P$1") (pintype "bidirectional"))
      (node (ref "D301") (pin "A") (pinfunction "A_A") (pintype "bidirectional"))
      (node (ref "D302") (pin "C") (pinfunction "CA_C") (pintype "bidirectional"))
      (node (ref "D503") (pin "1") (pinfunction "1_1") (pintype "bidirectional"))
      (node (ref "D504") (pin "P$1") (pinfunction "1_P$1") (pintype "bidirectional"))
      (node (ref "D505") (pin "P$1") (pinfunction "1_P$1") (pintype "bidirectional"))
      (node (ref "D506") (pin "P$1") (pinfunction "1_P$1") (pintype "bidirectional"))
      (node (ref "J201") (pin "5") (pinfunction "S_5") (pintype "passive"))
      (node (ref "J201") (pin "FIT@1") (pinfunction "S_FIT@1") (pintype "passive"))
      (node (ref "J201") (pin "FIT@2") (pinfunction "S_FIT@2") (pintype "passive"))
      (node (ref "J202") (pin "5") (pinfunction "S_5") (pintype "passive"))
      (node (ref "J202") (pin "FIT@1") (pinfunction "S_FIT@1") (pintype "passive"))
      (node (ref "J202") (pin "FIT@2") (pinfunction "S_FIT@2") (pintype "passive"))
      (node (ref "J203") (pin "5") (pinfunction "S_5") (pintype "passive"))
      (node (ref "J203") (pin "FIT@1") (pinfunction "S_FIT@1") (pintype "passive"))
      (node (ref "J203") (pin "FIT@2") (pinfunction "S_FIT@2") (pintype "passive"))
      (node (ref "J204") (pin "5") (pinfunction "S_5") (pintype "passive"))
      (node (ref "J204") (pin "FIT@1") (pinfunction "S_FIT@1") (pintype "passive"))
      (node (ref "J204") (pin "FIT@2") (pinfunction "S_FIT@2") (pintype "passive"))
      (node (ref "J205") (pin "5") (pinfunction "S_5") (pintype "passive"))
      (node (ref "J205") (pin "FIT@1") (pinfunction "S_FIT@1") (pintype "passive"))
      (node (ref "J205") (pin "FIT@2") (pinfunction "S_FIT@2") (pintype "passive"))
      (node (ref "J301") (pin "1") (pinfunction "S_1") (pintype "passive"))
      (node (ref "J302") (pin "2") (pinfunction "S_2") (pintype "passive"))
      (node (ref "J402") (pin "FIT@1") (pinfunction "S_FIT@1") (pintype "passive"))
      (node (ref "J402") (pin "FIT@2") (pinfunction "S_FIT@2") (pintype "passive"))
      (node (ref "J501") (pin "6") (pinfunction "S_6") (pintype "passive"))
      (node (ref "J501") (pin "FIT@1") (pinfunction "S_FIT@1") (pintype "passive"))
      (node (ref "J501") (pin "FIT@2") (pinfunction "S_FIT@2") (pintype "passive"))
      (node (ref "J502") (pin "3") (pinfunction "S_3") (pintype "passive"))
      (node (ref "J502") (pin "FIT@1") (pinfunction "S_FIT@1") (pintype "passive"))
      (node (ref "J502") (pin "FIT@2") (pinfunction "S_FIT@2") (pintype "passive"))
      (node (ref "J503") (pin "GND") (pinfunction "GND_GND") (pintype "bidirectional"))
      (node (ref "J503") (pin "GND@1") (pinfunction "CASE_GND@1") (pintype "bidirectional"))
      (node (ref "J503") (pin "GND@2") (pinfunction "CASE_GND@2") (pintype "bidirectional"))
      (node (ref "J503") (pin "GND@3") (pinfunction "CASE_GND@3") (pintype "bidirectional"))
      (node (ref "J503") (pin "GND@4") (pinfunction "CASE_GND@4") (pintype "bidirectional"))
      (node (ref "J504") (pin "2") (pinfunction "S_2") (pintype "passive"))
      (node (ref "J504") (pin "FIT@1") (pinfunction "S_FIT@1") (pintype "passive"))
      (node (ref "J504") (pin "FIT@2") (pinfunction "S_FIT@2") (pintype "passive"))
      (node (ref "J505") (pin "10") (pinfunction "S_10") (pintype "passive"))
      (node (ref "J505") (pin "6") (pinfunction "S_6") (pintype "passive"))
      (node (ref "J505") (pin "8") (pinfunction "S_8") (pintype "passive"))
      (node (ref "J505") (pin "TAB1") (pinfunction "S_TAB1") (pintype "passive"))
      (node (ref "J505") (pin "TAB2") (pinfunction "S_TAB2") (pintype "passive"))
      (node (ref "J506") (pin "3") (pinfunction "S_3") (pintype "passive"))
      (node (ref "J506") (pin "FIT@1") (pinfunction "S_FIT@1") (pintype "passive"))
      (node (ref "J506") (pin "FIT@2") (pinfunction "S_FIT@2") (pintype "passive"))
      (node (ref "P302") (pin "H1") (pinfunction "S_H1") (pintype "passive"))
      (node (ref "P302") (pin "H10") (pinfunction "S_H10") (pintype "passive"))
      (node (ref "P302") (pin "H11") (pinfunction "S_H11") (pintype "passive"))
      (node (ref "P302") (pin "H12") (pinfunction "S_H12") (pintype "passive"))
      (node (ref "P302") (pin "H2") (pinfunction "S_H2") (pintype "passive"))
      (node (ref "P302") (pin "H3") (pinfunction "S_H3") (pintype "passive"))
      (node (ref "P302") (pin "H4") (pinfunction "S_H4") (pintype "passive"))
      (node (ref "P302") (pin "H5") (pinfunction "S_H5") (pintype "passive"))
      (node (ref "P302") (pin "H6") (pinfunction "S_H6") (pintype "passive"))
      (node (ref "P302") (pin "H7") (pinfunction "S_H7") (pintype "passive"))
      (node (ref "P302") (pin "H8") (pinfunction "S_H8") (pintype "passive"))
      (node (ref "P302") (pin "H9") (pinfunction "S_H9") (pintype "passive"))
      (node (ref "P302") (pin "PAD") (pinfunction "S_PAD") (pintype "passive"))
      (node (ref "Q405") (pin "S1") (pinfunction "S1_S1") (pintype "bidirectional"))
      (node (ref "Q405") (pin "S2") (pinfunction "S1_S2") (pintype "bidirectional"))
      (node (ref "Q405") (pin "S3") (pinfunction "S1_S3") (pintype "bidirectional"))
      (node (ref "Q405") (pin "S4") (pinfunction "S1_S4") (pintype "bidirectional"))
      (node (ref "Q405") (pin "S5") (pinfunction "S1_S5") (pintype "bidirectional"))
      (node (ref "Q406") (pin "S1") (pinfunction "S1_S1") (pintype "bidirectional"))
      (node (ref "Q406") (pin "S2") (pinfunction "S1_S2") (pintype "bidirectional"))
      (node (ref "Q406") (pin "S3") (pinfunction "S1_S3") (pintype "bidirectional"))
      (node (ref "Q406") (pin "S4") (pinfunction "S1_S4") (pintype "bidirectional"))
      (node (ref "Q406") (pin "S5") (pinfunction "S1_S5") (pintype "bidirectional"))
      (node (ref "Q407") (pin "S1") (pinfunction "S1_S1") (pintype "bidirectional"))
      (node (ref "Q407") (pin "S2") (pinfunction "S1_S2") (pintype "bidirectional"))
      (node (ref "Q407") (pin "S3") (pinfunction "S1_S3") (pintype "bidirectional"))
      (node (ref "Q407") (pin "S4") (pinfunction "S1_S4") (pintype "bidirectional"))
      (node (ref "Q407") (pin "S5") (pinfunction "S1_S5") (pintype "bidirectional"))
      (node (ref "Q408") (pin "S1") (pinfunction "S1_S1") (pintype "bidirectional"))
      (node (ref "Q408") (pin "S2") (pinfunction "S1_S2") (pintype "bidirectional"))
      (node (ref "Q408") (pin "S3") (pinfunction "S1_S3") (pintype "bidirectional"))
      (node (ref "Q408") (pin "S4") (pinfunction "S1_S4") (pintype "bidirectional"))
      (node (ref "Q408") (pin "S5") (pinfunction "S1_S5") (pintype "bidirectional"))
      (node (ref "Q409") (pin "S1") (pinfunction "S1_S1") (pintype "bidirectional"))
      (node (ref "Q409") (pin "S2") (pinfunction "S1_S2") (pintype "bidirectional"))
      (node (ref "Q409") (pin "S3") (pinfunction "S1_S3") (pintype "bidirectional"))
      (node (ref "Q409") (pin "S4") (pinfunction "S1_S4") (pintype "bidirectional"))
      (node (ref "Q409") (pin "S5") (pinfunction "S1_S5") (pintype "bidirectional"))
      (node (ref "R104") (pin "P$1") (pinfunction "P$1_P$1") (pintype "bidirectional"))
      (node (ref "R105") (pin "P$1") (pinfunction "P$1_P$1") (pintype "bidirectional"))
      (node (ref "R107") (pin "P$1") (pinfunction "P$1_P$1") (pintype "bidirectional"))
      (node (ref "R108") (pin "P$1") (pinfunction "P$1_P$1") (pintype "bidirectional"))
      (node (ref "R110") (pin "P$1") (pinfunction "P$1_P$1") (pintype "bidirectional"))
      (node (ref "R114") (pin "P$2") (pinfunction "P$2_P$2") (pintype "bidirectional"))
      (node (ref "R116") (pin "P$1") (pinfunction "P$1_P$1") (pintype "bidirectional"))
      (node (ref "R118") (pin "P$1") (pinfunction "P$1_P$1") (pintype "bidirectional"))
      (node (ref "R121") (pin "P$1") (pinfunction "P$1_P$1") (pintype "bidirectional"))
      (node (ref "R302") (pin "P$1") (pinfunction "P$1_P$1") (pintype "bidirectional"))
      (node (ref "R304") (pin "P$1") (pinfunction "P$1_P$1") (pintype "bidirectional"))
      (node (ref "R401") (pin "P$1") (pinfunction "P$1_P$1") (pintype "bidirectional"))
      (node (ref "R402") (pin "P$1") (pinfunction "P$1_P$1") (pintype "bidirectional"))
      (node (ref "R403") (pin "P$1") (pinfunction "P$1_P$1") (pintype "bidirectional"))
      (node (ref "R404") (pin "P$1") (pinfunction "P$1_P$1") (pintype "bidirectional"))
      (node (ref "R405") (pin "P$1") (pinfunction "P$1_P$1") (pintype "bidirectional"))
      (node (ref "R406") (pin "P$1") (pinfunction "P$1_P$1") (pintype "bidirectional"))
      (node (ref "R407") (pin "P$1") (pinfunction "P$1_P$1") (pintype "bidirectional"))
      (node (ref "R408") (pin "P$1") (pinfunction "P$1_P$1") (pintype "bidirectional"))
      (node (ref "R428") (pin "P$1") (pinfunction "P$1_P$1") (pintype "bidirectional"))
      (node (ref "R430") (pin "P$1") (pinfunction "P$1_P$1") (pintype "bidirectional"))
      (node (ref "R505") (pin "P$1") (pinfunction "P$1_P$1") (pintype "bidirectional"))
      (node (ref "R507") (pin "P$2") (pinfunction "P$2_P$2") (pintype "bidirectional"))
      (node (ref "R510") (pin "P$1") (pinfunction "P$1_P$1") (pintype "bidirectional"))
      (node (ref "R511") (pin "P$1") (pinfunction "P$1_P$1") (pintype "bidirectional"))
      (node (ref "U101") (pin "3") (pinfunction "GND_3") (pintype "bidirectional"))
      (node (ref "U102") (pin "14") (pinfunction "GND_14") (pintype "bidirectional"))
      (node (ref "U102") (pin "24") (pinfunction "GNDA_24") (pintype "bidirectional"))
      (node (ref "U102") (pin "3") (pinfunction "GND_3") (pintype "bidirectional"))
      (node (ref "U102") (pin "44") (pinfunction "GND_44") (pintype "bidirectional"))
      (node (ref "U102") (pin "53") (pinfunction "PLL_GND_53") (pintype "bidirectional"))
      (node (ref "U102") (pin "54") (pinfunction "TEST_54") (pintype "bidirectional"))
      (node (ref "U102") (pin "62") (pinfunction "GND_62") (pintype "bidirectional"))
      (node (ref "U102") (pin "73") (pinfunction "GND_73") (pintype "bidirectional"))
      (node (ref "U102") (pin "PAD") (pinfunction "GNDP_PAD") (pintype "bidirectional"))
      (node (ref "U201") (pin "2") (pinfunction "GND_2") (pintype "bidirectional"))
      (node (ref "U202") (pin "2") (pinfunction "GND_2") (pintype "bidirectional"))
      (node (ref "U203") (pin "2") (pinfunction "GND_2") (pintype "bidirectional"))
      (node (ref "U204") (pin "2") (pinfunction "GND_2") (pintype "bidirectional"))
      (node (ref "U205") (pin "4") (pinfunction "GND_4") (pintype "bidirectional"))
      (node (ref "U206") (pin "4") (pinfunction "GND_4") (pintype "bidirectional"))
      (node (ref "U207") (pin "4") (pinfunction "GND_4") (pintype "bidirectional"))
      (node (ref "U208") (pin "4") (pinfunction "GND_4") (pintype "bidirectional"))
      (node (ref "U301") (pin "2") (pinfunction "GND_2") (pintype "bidirectional"))
      (node (ref "U301") (pin "4") (pinfunction "SHDN_4") (pintype "bidirectional"))
      (node (ref "U301") (pin "6") (pinfunction "GND_6") (pintype "bidirectional"))
      (node (ref "U301") (pin "7") (pinfunction "GND_7") (pintype "bidirectional"))
      (node (ref "U302") (pin "5") (pinfunction "GND_5") (pintype "bidirectional"))
      (node (ref "U302") (pin "6") (pinfunction "GND_6") (pintype "bidirectional"))
      (node (ref "U302") (pin "7") (pinfunction "GND_7") (pintype "bidirectional"))
      (node (ref "U302") (pin "8") (pinfunction "GND_8") (pintype "bidirectional"))
      (node (ref "U303") (pin "5") (pinfunction "GND_5") (pintype "bidirectional"))
      (node (ref "U303") (pin "6") (pinfunction "GND_6") (pintype "bidirectional"))
      (node (ref "U303") (pin "7") (pinfunction "GND_7") (pintype "bidirectional"))
      (node (ref "U303") (pin "8") (pinfunction "GND_8") (pintype "bidirectional"))
      (node (ref "U401") (pin "4") (pinfunction "GNDI_4") (pintype "bidirectional"))
      (node (ref "U401") (pin "9") (pinfunction "GNB_9") (pintype "bidirectional"))
      (node (ref "U402") (pin "4") (pinfunction "GNDI_4") (pintype "bidirectional"))
      (node (ref "U402") (pin "9") (pinfunction "GNB_9") (pintype "bidirectional"))
      (node (ref "U403") (pin "4") (pinfunction "GNDI_4") (pintype "bidirectional"))
      (node (ref "U403") (pin "9") (pinfunction "GNB_9") (pintype "bidirectional"))
      (node (ref "U404") (pin "4") (pinfunction "GNDI_4") (pintype "bidirectional"))
      (node (ref "U404") (pin "9") (pinfunction "GNB_9") (pintype "bidirectional"))
      (node (ref "U405") (pin "2") (pinfunction "P$1_2") (pintype "bidirectional"))
      (node (ref "U405") (pin "3") (pinfunction "P$1_3") (pintype "bidirectional"))
      (node (ref "U406") (pin "2") (pinfunction "P$1_2") (pintype "bidirectional"))
      (node (ref "U406") (pin "3") (pinfunction "P$1_3") (pintype "bidirectional"))
      (node (ref "U407") (pin "3") (pinfunction "CA_3") (pintype "bidirectional"))
      (node (ref "U407") (pin "5") (pinfunction "GNB_5") (pintype "bidirectional"))
      (node (ref "U501") (pin "2") (pinfunction "GND_2") (pintype "bidirectional"))
      (node (ref "U501") (pin "PAD") (pinfunction "GNDP_PAD") (pintype "bidirectional"))
    )
    (net (code "32") (name "HALL_UX") (class "Default")
      (node (ref "U102") (pin "38") (pinfunction "HALL_UX_38") (pintype "bidirectional"))
      (node (ref "U207") (pin "2") (pinfunction "Y_2") (pintype "output"))
    )
    (net (code "33") (name "HALL_V") (class "Default")
      (node (ref "U102") (pin "37") (pinfunction "HALL_V_37") (pintype "bidirectional"))
      (node (ref "U207") (pin "5") (pinfunction "Y_5") (pintype "output"))
    )
    (net (code "34") (name "HALL_WY") (class "Default")
      (node (ref "U102") (pin "36") (pinfunction "HALL_WY_36") (pintype "bidirectional"))
      (node (ref "U207") (pin "7") (pinfunction "Y_7") (pintype "output"))
    )
    (net (code "35") (name "INT") (class "Default")
      (node (ref "J501") (pin "5") (pinfunction "S_5") (pintype "passive"))
      (node (ref "JP507") (pin "2") (pinfunction "2_2") (pintype "passive"))
      (node (ref "U102") (pin "12") (pinfunction "STATUS_12") (pintype "bidirectional"))
    )
    (net (code "36") (name "MISO") (class "Default")
      (node (ref "J501") (pin "4") (pinfunction "S_4") (pintype "passive"))
      (node (ref "JP501") (pin "2") (pinfunction "2_2") (pintype "passive"))
      (node (ref "U102") (pin "9") (pinfunction "SPI_MISO_9") (pintype "bidirectional"))
    )
    (net (code "37") (name "MOSI") (class "Default")
      (node (ref "J501") (pin "3") (pinfunction "S_3") (pintype "passive"))
      (node (ref "JP502") (pin "2") (pinfunction "2_2") (pintype "passive"))
      (node (ref "U102") (pin "8") (pinfunction "SPI_MOSI_8") (pintype "bidirectional"))
    )
    (net (code "38") (name "Net-(C307-AN)") (class "Default")
      (node (ref "C305") (pin "P$1") (pinfunction "P$1_P$1") (pintype "bidirectional"))
      (node (ref "C307") (pin "+") (pinfunction "AN_+") (pintype "bidirectional"))
      (node (ref "L301") (pin "2") (pinfunction "P$2_2") (pintype "bidirectional"))
      (node (ref "R303") (pin "P$2") (pinfunction "P$2_P$2") (pintype "bidirectional"))
      (node (ref "R305") (pin "P$2") (pinfunction "P$2_P$2") (pintype "bidirectional"))
      (node (ref "U302") (pin "1") (pinfunction "EN_1") (pintype "bidirectional"))
      (node (ref "U302") (pin "2") (pinfunction "VIN_2") (pintype "bidirectional"))
      (node (ref "U303") (pin "1") (pinfunction "EN_1") (pintype "bidirectional"))
      (node (ref "U303") (pin "2") (pinfunction "VIN_2") (pintype "bidirectional"))
    )
    (net (code "39") (name "Net-(D101-3)") (class "Default")
      (node (ref "C118") (pin "P$1") (pinfunction "P$1_P$1") (pintype "bidirectional"))
      (node (ref "D101") (pin "P$3") (pinfunction "3_P$3") (pintype "bidirectional"))
      (node (ref "R116") (pin "P$2") (pinfunction "P$2_P$2") (pintype "bidirectional"))
      (node (ref "R119") (pin "P$1") (pinfunction "P$1_P$1") (pintype "bidirectional"))
      (node (ref "U102") (pin "20") (pinfunction "ADC_VM_20") (pintype "bidirectional"))
    )
    (net (code "40") (name "Net-(D302-AN)") (class "Default")
      (node (ref "D302") (pin "A") (pinfunction "AN_A") (pintype "bidirectional"))
      (node (ref "R305") (pin "P$1") (pinfunction "P$1_P$1") (pintype "bidirectional"))
      (node (ref "U302") (pin "4") (pinfunction "FLG_4") (pintype "bidirectional"))
      (node (ref "U303") (pin "4") (pinfunction "FLG_4") (pintype "bidirectional"))
    )
    (net (code "41") (name "Net-(D401-PadA)") (class "Default")
      (node (ref "D401") (pin "A") (pinfunction "A_A") (pintype "passive"))
      (node (ref "R409") (pin "P$2") (pinfunction "P$2_P$2") (pintype "bidirectional"))
    )
    (net (code "42") (name "Net-(D402-PadA)") (class "Default")
      (node (ref "D402") (pin "A") (pinfunction "A_A") (pintype "passive"))
      (node (ref "R410") (pin "P$2") (pinfunction "P$2_P$2") (pintype "bidirectional"))
    )
    (net (code "43") (name "Net-(D403-PadA)") (class "Default")
      (node (ref "D403") (pin "A") (pinfunction "A_A") (pintype "passive"))
      (node (ref "R411") (pin "P$2") (pinfunction "P$2_P$2") (pintype "bidirectional"))
    )
    (net (code "44") (name "Net-(D404-PadA)") (class "Default")
      (node (ref "D404") (pin "A") (pinfunction "A_A") (pintype "passive"))
      (node (ref "R412") (pin "P$2") (pinfunction "P$2_P$2") (pintype "bidirectional"))
    )
    (net (code "45") (name "Net-(D501-AN)") (class "Default")
      (node (ref "D501") (pin "A") (pinfunction "AN_A") (pintype "bidirectional"))
      (node (ref "R502") (pin "P$1") (pinfunction "P$1_P$1") (pintype "bidirectional"))
    )
    (net (code "46") (name "Net-(D501-CA)") (class "Default")
      (node (ref "D501") (pin "C") (pinfunction "CA_C") (pintype "bidirectional"))
      (node (ref "U501") (pin "14") (pinfunction "(GPIO0-TXT)GPIO7-~{CS7}_14") (pintype "bidirectional"))
    )
    (net (code "47") (name "Net-(D502-AN)") (class "Default")
      (node (ref "D502") (pin "A") (pinfunction "AN_A") (pintype "bidirectional"))
      (node (ref "R503") (pin "P$1") (pinfunction "P$1_P$1") (pintype "bidirectional"))
    )
    (net (code "48") (name "Net-(D502-CA)") (class "Default")
      (node (ref "D502") (pin "C") (pinfunction "CA_C") (pintype "bidirectional"))
      (node (ref "U501") (pin "13") (pinfunction "(GPIO1-RXT)GPIO8-~{CS8}-SPIACT_13") (pintype "bidirectional"))
    )
    (net (code "49") (name "Net-(D503-Pad4)") (class "Default")
      (node (ref "D503") (pin "4") (pinfunction "4_4") (pintype "bidirectional"))
      (node (ref "J503") (pin "VBUS") (pinfunction "VBUS_VBUS") (pintype "bidirectional"))
      (node (ref "R506") (pin "P$1") (pinfunction "P$1_P$1") (pintype "bidirectional"))
    )
    (net (code "50") (name "Net-(J201B-S)") (class "Default")
      (node (ref "J201") (pin "2") (pinfunction "S_2") (pintype "passive"))
      (node (ref "R201") (pin "P$1") (pinfunction "P$1_P$1") (pintype "bidirectional"))
    )
    (net (code "51") (name "Net-(J201C-S)") (class "Default")
      (node (ref "J201") (pin "3") (pinfunction "S_3") (pintype "passive"))
      (node (ref "R202") (pin "P$1") (pinfunction "P$1_P$1") (pintype "bidirectional"))
    )
    (net (code "52") (name "Net-(J201D-S)") (class "Default")
      (node (ref "J201") (pin "4") (pinfunction "S_4") (pintype "passive"))
      (node (ref "R203") (pin "P$1") (pinfunction "P$1_P$1") (pintype "bidirectional"))
    )
    (net (code "53") (name "Net-(J202B-S)") (class "Default")
      (node (ref "J202") (pin "2") (pinfunction "S_2") (pintype "passive"))
      (node (ref "R204") (pin "P$1") (pinfunction "P$1_P$1") (pintype "bidirectional"))
    )
    (net (code "54") (name "Net-(J202C-S)") (class "Default")
      (node (ref "J202") (pin "3") (pinfunction "S_3") (pintype "passive"))
      (node (ref "R205") (pin "P$1") (pinfunction "P$1_P$1") (pintype "bidirectional"))
    )
    (net (code "55") (name "Net-(J202D-S)") (class "Default")
      (node (ref "J202") (pin "4") (pinfunction "S_4") (pintype "passive"))
      (node (ref "R206") (pin "P$1") (pinfunction "P$1_P$1") (pintype "bidirectional"))
    )
    (net (code "56") (name "Net-(J203B-S)") (class "Default")
      (node (ref "J203") (pin "2") (pinfunction "S_2") (pintype "passive"))
      (node (ref "R207") (pin "P$1") (pinfunction "P$1_P$1") (pintype "bidirectional"))
    )
    (net (code "57") (name "Net-(J203C-S)") (class "Default")
      (node (ref "J203") (pin "3") (pinfunction "S_3") (pintype "passive"))
      (node (ref "R208") (pin "P$1") (pinfunction "P$1_P$1") (pintype "bidirectional"))
    )
    (net (code "58") (name "Net-(J203D-S)") (class "Default")
      (node (ref "J203") (pin "4") (pinfunction "S_4") (pintype "passive"))
      (node (ref "R209") (pin "P$1") (pinfunction "P$1_P$1") (pintype "bidirectional"))
    )
    (net (code "59") (name "Net-(J204B-S)") (class "Default")
      (node (ref "J204") (pin "2") (pinfunction "S_2") (pintype "passive"))
      (node (ref "R210") (pin "P$1") (pinfunction "P$1_P$1") (pintype "bidirectional"))
    )
    (net (code "60") (name "Net-(J204C-S)") (class "Default")
      (node (ref "J204") (pin "3") (pinfunction "S_3") (pintype "passive"))
      (node (ref "R211") (pin "P$1") (pinfunction "P$1_P$1") (pintype "bidirectional"))
    )
    (net (code "61") (name "Net-(J204D-S)") (class "Default")
      (node (ref "J204") (pin "4") (pinfunction "S_4") (pintype "passive"))
      (node (ref "R212") (pin "P$1") (pinfunction "P$1_P$1") (pintype "bidirectional"))
    )
    (net (code "62") (name "Net-(J205B-S)") (class "Default")
      (node (ref "J205") (pin "2") (pinfunction "S_2") (pintype "passive"))
      (node (ref "R213") (pin "P$1") (pinfunction "P$1_P$1") (pintype "bidirectional"))
    )
    (net (code "63") (name "Net-(J205C-S)") (class "Default")
      (node (ref "J205") (pin "3") (pinfunction "S_3") (pintype "passive"))
      (node (ref "R218") (pin "P$1") (pinfunction "P$1_P$1") (pintype "bidirectional"))
    )
    (net (code "64") (name "Net-(J205D-S)") (class "Default")
      (node (ref "J205") (pin "4") (pinfunction "S_4") (pintype "passive"))
      (node (ref "R227") (pin "P$1") (pinfunction "P$1_P$1") (pintype "bidirectional"))
    )
    (net (code "65") (name "Net-(J403B-S)") (class "Default")
      (node (ref "J403") (pin "2") (pinfunction "S_2") (pintype "passive"))
      (node (ref "P406") (pin "H1") (pinfunction "S_H1") (pintype "passive"))
      (node (ref "P406") (pin "H10") (pinfunction "S_H10") (pintype "passive"))
      (node (ref "P406") (pin "H11") (pinfunction "S_H11") (pintype "passive"))
      (node (ref "P406") (pin "H12") (pinfunction "S_H12") (pintype "passive"))
      (node (ref "P406") (pin "H2") (pinfunction "S_H2") (pintype "passive"))
      (node (ref "P406") (pin "H3") (pinfunction "S_H3") (pintype "passive"))
      (node (ref "P406") (pin "H4") (pinfunction "S_H4") (pintype "passive"))
      (node (ref "P406") (pin "H5") (pinfunction "S_H5") (pintype "passive"))
      (node (ref "P406") (pin "H6") (pinfunction "S_H6") (pintype "passive"))
      (node (ref "P406") (pin "H7") (pinfunction "S_H7") (pintype "passive"))
      (node (ref "P406") (pin "H8") (pinfunction "S_H8") (pintype "passive"))
      (node (ref "P406") (pin "H9") (pinfunction "S_H9") (pintype "passive"))
      (node (ref "P406") (pin "PAD") (pinfunction "S_PAD") (pintype "passive"))
      (node (ref "Q409") (pin "D1") (pinfunction "D1_D1") (pintype "bidirectional"))
      (node (ref "Q409") (pin "D2") (pinfunction "D1_D2") (pintype "bidirectional"))
      (node (ref "Q409") (pin "D3") (pinfunction "D1_D3") (pintype "bidirectional"))
      (node (ref "Q409") (pin "D4") (pinfunction "D1_D4") (pintype "bidirectional"))
    )
    (net (code "66") (name "Net-(J504A-S)") (class "Default")
      (node (ref "J504") (pin "1") (pinfunction "S_1") (pintype "passive"))
      (node (ref "R504") (pin "P$1") (pinfunction "P$1_P$1") (pintype "bidirectional"))
    )
    (net (code "67") (name "Net-(J506A-S)") (class "Default")
      (node (ref "J506") (pin "1") (pinfunction "S_1") (pintype "passive"))
      (node (ref "R508") (pin "P$1") (pinfunction "P$1_P$1") (pintype "bidirectional"))
    )
    (net (code "68") (name "Net-(J506B-S)") (class "Default")
      (node (ref "J506") (pin "2") (pinfunction "S_2") (pintype "passive"))
      (node (ref "R509") (pin "P$1") (pinfunction "P$1_P$1") (pintype "bidirectional"))
    )
    (net (code "69") (name "Net-(L301-P$1)") (class "Default")
      (node (ref "D301") (pin "C") (pinfunction "C_C") (pintype "bidirectional"))
      (node (ref "L301") (pin "1") (pinfunction "P$1_1") (pintype "bidirectional"))
      (node (ref "U301") (pin "8") (pinfunction "SW_8") (pintype "bidirectional"))
    )
    (net (code "70") (name "Net-(Q401-G1)") (class "Default")
      (node (ref "Q401") (pin "G") (pinfunction "G1_G") (pintype "bidirectional"))
      (node (ref "R413") (pin "P$2") (pinfunction "P$2_P$2") (pintype "bidirectional"))
    )
    (net (code "71") (name "Net-(Q402-G1)") (class "Default")
      (node (ref "Q402") (pin "G") (pinfunction "G1_G") (pintype "bidirectional"))
      (node (ref "R414") (pin "P$2") (pinfunction "P$2_P$2") (pintype "bidirectional"))
    )
    (net (code "72") (name "Net-(Q403-G1)") (class "Default")
      (node (ref "Q403") (pin "G") (pinfunction "G1_G") (pintype "bidirectional"))
      (node (ref "R415") (pin "P$2") (pinfunction "P$2_P$2") (pintype "bidirectional"))
    )
    (net (code "73") (name "Net-(Q404-G1)") (class "Default")
      (node (ref "Q404") (pin "G") (pinfunction "G1_G") (pintype "bidirectional"))
      (node (ref "R416") (pin "P$2") (pinfunction "P$2_P$2") (pintype "bidirectional"))
    )
    (net (code "74") (name "Net-(Q405-G1)") (class "Default")
      (node (ref "Q405") (pin "G") (pinfunction "G1_G") (pintype "bidirectional"))
      (node (ref "R417") (pin "P$2") (pinfunction "P$2_P$2") (pintype "bidirectional"))
    )
    (net (code "75") (name "Net-(Q406-G1)") (class "Default")
      (node (ref "Q406") (pin "G") (pinfunction "G1_G") (pintype "bidirectional"))
      (node (ref "R418") (pin "P$2") (pinfunction "P$2_P$2") (pintype "bidirectional"))
    )
    (net (code "76") (name "Net-(Q407-G1)") (class "Default")
      (node (ref "Q407") (pin "G") (pinfunction "G1_G") (pintype "bidirectional"))
      (node (ref "R419") (pin "P$2") (pinfunction "P$2_P$2") (pintype "bidirectional"))
    )
    (net (code "77") (name "Net-(Q408-G1)") (class "Default")
      (node (ref "Q408") (pin "G") (pinfunction "G1_G") (pintype "bidirectional"))
      (node (ref "R420") (pin "P$2") (pinfunction "P$2_P$2") (pintype "bidirectional"))
    )
    (net (code "78") (name "Net-(Q409-G1)") (class "Default")
      (node (ref "Q409") (pin "G") (pinfunction "G1_G") (pintype "bidirectional"))
      (node (ref "R431") (pin "P$2") (pinfunction "P$2_P$2") (pintype "bidirectional"))
    )
    (net (code "79") (name "Net-(R421-PadSENSE+)") (class "Default")
      (node (ref "R421") (pin "SENSE+") (pinfunction "SENSE+_SENSE+") (pintype "bidirectional"))
      (node (ref "R424") (pin "P$1") (pinfunction "P$1_P$1") (pintype "bidirectional"))
    )
    (net (code "80") (name "Net-(R421-PadSENSE-)") (class "Default")
      (node (ref "R421") (pin "SENSE-") (pinfunction "SENSE-_SENSE-") (pintype "bidirectional"))
      (node (ref "R423") (pin "P$1") (pinfunction "P$1_P$1") (pintype "bidirectional"))
    )
    (net (code "81") (name "Net-(R422-PadSENSE+)") (class "Default")
      (node (ref "R422") (pin "SENSE+") (pinfunction "SENSE+_SENSE+") (pintype "bidirectional"))
      (node (ref "R426") (pin "P$1") (pinfunction "P$1_P$1") (pintype "bidirectional"))
    )
    (net (code "82") (name "Net-(R422-PadSENSE-)") (class "Default")
      (node (ref "R422") (pin "SENSE-") (pinfunction "SENSE-_SENSE-") (pintype "bidirectional"))
      (node (ref "R425") (pin "P$1") (pinfunction "P$1_P$1") (pintype "bidirectional"))
    )
    (net (code "83") (name "Net-(R431-PadP$1)") (class "Default")
      (node (ref "R431") (pin "P$1") (pinfunction "P$1_P$1") (pintype "bidirectional"))
      (node (ref "U407") (pin "6") (pinfunction "VO_6") (pintype "bidirectional"))
      (node (ref "U407") (pin "7") (pinfunction "VO_7") (pintype "bidirectional"))
    )
    (net (code "84") (name "Net-(U101-EN)") (class "Default")
      (node (ref "R101") (pin "P$1") (pinfunction "P$1_P$1") (pintype "bidirectional"))
      (node (ref "U101") (pin "1") (pinfunction "EN_1") (pintype "bidirectional"))
    )
    (net (code "85") (name "Net-(U101-OUT)") (class "Default")
      (node (ref "U101") (pin "4") (pinfunction "OUT_4") (pintype "bidirectional"))
      (node (ref "U102") (pin "51") (pinfunction "CLK_51") (pintype "bidirectional"))
    )
    (net (code "86") (name "Net-(U102A-AGPI_A)") (class "Default")
      (node (ref "C114") (pin "P$1") (pinfunction "P$1_P$1") (pintype "bidirectional"))
      (node (ref "R111") (pin "P$1") (pinfunction "P$1_P$1") (pintype "bidirectional"))
      (node (ref "U102") (pin "21") (pinfunction "AGPI_A_21") (pintype "bidirectional"))
    )
    (net (code "87") (name "Net-(U102A-AGPI_B)") (class "Default")
      (node (ref "C115") (pin "P$1") (pinfunction "P$1_P$1") (pintype "bidirectional"))
      (node (ref "R112") (pin "P$2") (pinfunction "P$2_P$2") (pintype "bidirectional"))
      (node (ref "U102") (pin "22") (pinfunction "AGPI_B_22") (pintype "bidirectional"))
    )
    (net (code "88") (name "Net-(U102B-~{RST})") (class "Default")
      (node (ref "R102") (pin "P$2") (pinfunction "P$2_P$2") (pintype "bidirectional"))
      (node (ref "U102") (pin "50") (pinfunction "~{RST}_50") (pintype "bidirectional"))
    )
    (net (code "89") (name "Net-(U102D-ADC_I0_NEG)") (class "Default")
      (node (ref "R117") (pin "P$1") (pinfunction "P$1_P$1") (pintype "bidirectional"))
      (node (ref "R118") (pin "P$2") (pinfunction "P$2_P$2") (pintype "bidirectional"))
      (node (ref "U102") (pin "17") (pinfunction "ADC_I0_NEG_17") (pintype "bidirectional"))
    )
    (net (code "90") (name "Net-(U102D-ADC_I0_POS)") (class "Default")
      (node (ref "C116") (pin "P$1") (pinfunction "P$1_P$1") (pintype "bidirectional"))
      (node (ref "R113") (pin "P$1") (pinfunction "P$1_P$1") (pintype "bidirectional"))
      (node (ref "U102") (pin "16") (pinfunction "ADC_I0_POS_16") (pintype "bidirectional"))
    )
    (net (code "91") (name "Net-(U102D-ADC_I1_NEG)") (class "Default")
      (node (ref "R120") (pin "P$1") (pinfunction "P$1_P$1") (pintype "bidirectional"))
      (node (ref "R121") (pin "P$2") (pinfunction "P$2_P$2") (pintype "bidirectional"))
      (node (ref "U102") (pin "19") (pinfunction "ADC_I1_NEG_19") (pintype "bidirectional"))
    )
    (net (code "92") (name "Net-(U102D-ADC_I1_POS)") (class "Default")
      (node (ref "C117") (pin "P$1") (pinfunction "P$1_P$1") (pintype "bidirectional"))
      (node (ref "R115") (pin "P$1") (pinfunction "P$1_P$1") (pintype "bidirectional"))
      (node (ref "U102") (pin "18") (pinfunction "ADC_I1_POS_18") (pintype "bidirectional"))
    )
    (net (code "93") (name "Net-(U102D-AENC_UX_NEG)") (class "Default")
      (node (ref "R103") (pin "P$1") (pinfunction "P$1_P$1") (pintype "bidirectional"))
      (node (ref "R104") (pin "P$2") (pinfunction "P$2_P$2") (pintype "bidirectional"))
      (node (ref "U102") (pin "26") (pinfunction "AENC_UX_NEG_26") (pintype "bidirectional"))
    )
    (net (code "94") (name "Net-(U102D-AENC_VN_NEG)") (class "Default")
      (node (ref "R106") (pin "P$1") (pinfunction "P$1_P$1") (pintype "bidirectional"))
      (node (ref "R107") (pin "P$2") (pinfunction "P$2_P$2") (pintype "bidirectional"))
      (node (ref "U102") (pin "28") (pinfunction "AENC_VN_NEG_28") (pintype "bidirectional"))
    )
    (net (code "95") (name "Net-(U102D-AENC_WY_NEG)") (class "Default")
      (node (ref "R109") (pin "P$1") (pinfunction "P$1_P$1") (pintype "bidirectional"))
      (node (ref "R110") (pin "P$2") (pinfunction "P$2_P$2") (pintype "bidirectional"))
      (node (ref "U102") (pin "30") (pinfunction "AENC_WY_NEG_30") (pintype "bidirectional"))
    )
    (net (code "96") (name "Net-(U102D-PWM_IDLE_H)") (class "Default")
      (node (ref "R105") (pin "P$2") (pinfunction "P$2_P$2") (pintype "bidirectional"))
      (node (ref "U102") (pin "59") (pinfunction "PWM_IDLE_H_59") (pintype "bidirectional"))
    )
    (net (code "97") (name "Net-(U102D-PWM_IDLE_L)") (class "Default")
      (node (ref "R108") (pin "P$2") (pinfunction "P$2_P$2") (pintype "bidirectional"))
      (node (ref "U102") (pin "60") (pinfunction "PWM_IDLE_L_60") (pintype "bidirectional"))
    )
    (net (code "98") (name "Net-(U201-1)") (class "Default")
      (node (ref "C206") (pin "P$1") (pinfunction "P$1_P$1") (pintype "bidirectional"))
      (node (ref "R201") (pin "P$2") (pinfunction "P$2_P$2") (pintype "bidirectional"))
      (node (ref "R214") (pin "P$2") (pinfunction "P$2_P$2") (pintype "bidirectional"))
      (node (ref "U201") (pin "6") (pinfunction "1_6") (pintype "bidirectional"))
      (node (ref "U205") (pin "1") (pinfunction "A_1") (pintype "input"))
    )
    (net (code "99") (name "Net-(U201-2)") (class "Default")
      (node (ref "C218") (pin "P$1") (pinfunction "P$1_P$1") (pintype "bidirectional"))
      (node (ref "R203") (pin "P$2") (pinfunction "P$2_P$2") (pintype "bidirectional"))
      (node (ref "R223") (pin "P$2") (pinfunction "P$2_P$2") (pintype "bidirectional"))
      (node (ref "U201") (pin "1") (pinfunction "2_1") (pintype "bidirectional"))
      (node (ref "U205") (pin "6") (pinfunction "A_6") (pintype "input"))
    )
    (net (code "100") (name "Net-(U202-1)") (class "Default")
      (node (ref "C207") (pin "P$1") (pinfunction "P$1_P$1") (pintype "bidirectional"))
      (node (ref "R204") (pin "P$2") (pinfunction "P$2_P$2") (pintype "bidirectional"))
      (node (ref "R215") (pin "P$2") (pinfunction "P$2_P$2") (pintype "bidirectional"))
      (node (ref "U202") (pin "6") (pinfunction "1_6") (pintype "bidirectional"))
      (node (ref "U206") (pin "1") (pinfunction "A_1") (pintype "input"))
    )
    (net (code "101") (name "Net-(U202-2)") (class "Default")
      (node (ref "C219") (pin "P$1") (pinfunction "P$1_P$1") (pintype "bidirectional"))
      (node (ref "R206") (pin "P$2") (pinfunction "P$2_P$2") (pintype "bidirectional"))
      (node (ref "R224") (pin "P$2") (pinfunction "P$2_P$2") (pintype "bidirectional"))
      (node (ref "U202") (pin "1") (pinfunction "2_1") (pintype "bidirectional"))
      (node (ref "U206") (pin "6") (pinfunction "A_6") (pintype "input"))
    )
    (net (code "102") (name "Net-(U203-1)") (class "Default")
      (node (ref "C208") (pin "P$1") (pinfunction "P$1_P$1") (pintype "bidirectional"))
      (node (ref "R207") (pin "P$2") (pinfunction "P$2_P$2") (pintype "bidirectional"))
      (node (ref "R216") (pin "P$2") (pinfunction "P$2_P$2") (pintype "bidirectional"))
      (node (ref "U203") (pin "6") (pinfunction "1_6") (pintype "bidirectional"))
      (node (ref "U207") (pin "1") (pinfunction "A_1") (pintype "input"))
    )
    (net (code "103") (name "Net-(U203-2)") (class "Default")
      (node (ref "C220") (pin "P$1") (pinfunction "P$1_P$1") (pintype "bidirectional"))
      (node (ref "R209") (pin "P$2") (pinfunction "P$2_P$2") (pintype "bidirectional"))
      (node (ref "R225") (pin "P$2") (pinfunction "P$2_P$2") (pintype "bidirectional"))
      (node (ref "U203") (pin "1") (pinfunction "2_1") (pintype "bidirectional"))
      (node (ref "U207") (pin "6") (pinfunction "A_6") (pintype "input"))
    )
    (net (code "104") (name "Net-(U204-1)") (class "Default")
      (node (ref "C209") (pin "P$1") (pinfunction "P$1_P$1") (pintype "bidirectional"))
      (node (ref "R210") (pin "P$2") (pinfunction "P$2_P$2") (pintype "bidirectional"))
      (node (ref "R217") (pin "P$2") (pinfunction "P$2_P$2") (pintype "bidirectional"))
      (node (ref "U204") (pin "6") (pinfunction "1_6") (pintype "bidirectional"))
      (node (ref "U208") (pin "1") (pinfunction "A_1") (pintype "input"))
    )
    (net (code "105") (name "Net-(U204-2)") (class "Default")
      (node (ref "C221") (pin "P$1") (pinfunction "P$1_P$1") (pintype "bidirectional"))
      (node (ref "R212") (pin "P$2") (pinfunction "P$2_P$2") (pintype "bidirectional"))
      (node (ref "R226") (pin "P$2") (pinfunction "P$2_P$2") (pintype "bidirectional"))
      (node (ref "U204") (pin "1") (pinfunction "2_1") (pintype "bidirectional"))
      (node (ref "U208") (pin "6") (pinfunction "A_6") (pintype "input"))
    )
    (net (code "106") (name "Net-(U205B-A)") (class "Default")
      (node (ref "C210") (pin "P$1") (pinfunction "P$1_P$1") (pintype "bidirectional"))
      (node (ref "R202") (pin "P$2") (pinfunction "P$2_P$2") (pintype "bidirectional"))
      (node (ref "R219") (pin "P$2") (pinfunction "P$2_P$2") (pintype "bidirectional"))
      (node (ref "U201") (pin "4") (pinfunction "4_4") (pintype "bidirectional"))
      (node (ref "U205") (pin "3") (pinfunction "A_3") (pintype "input"))
    )
    (net (code "107") (name "Net-(U206B-A)") (class "Default")
      (node (ref "C211") (pin "P$1") (pinfunction "P$1_P$1") (pintype "bidirectional"))
      (node (ref "R205") (pin "P$2") (pinfunction "P$2_P$2") (pintype "bidirectional"))
      (node (ref "R220") (pin "P$2") (pinfunction "P$2_P$2") (pintype "bidirectional"))
      (node (ref "U202") (pin "4") (pinfunction "4_4") (pintype "bidirectional"))
      (node (ref "U206") (pin "3") (pinfunction "A_3") (pintype "input"))
    )
    (net (code "108") (name "Net-(U207B-A)") (class "Default")
      (node (ref "C212") (pin "P$1") (pinfunction "P$1_P$1") (pintype "bidirectional"))
      (node (ref "R208") (pin "P$2") (pinfunction "P$2_P$2") (pintype "bidirectional"))
      (node (ref "R221") (pin "P$2") (pinfunction "P$2_P$2") (pintype "bidirectional"))
      (node (ref "U203") (pin "4") (pinfunction "4_4") (pintype "bidirectional"))
      (node (ref "U207") (pin "3") (pinfunction "A_3") (pintype "input"))
    )
    (net (code "109") (name "Net-(U208B-A)") (class "Default")
      (node (ref "C213") (pin "P$1") (pinfunction "P$1_P$1") (pintype "bidirectional"))
      (node (ref "R211") (pin "P$2") (pinfunction "P$2_P$2") (pintype "bidirectional"))
      (node (ref "R222") (pin "P$2") (pinfunction "P$2_P$2") (pintype "bidirectional"))
      (node (ref "U204") (pin "4") (pinfunction "4_4") (pintype "bidirectional"))
      (node (ref "U208") (pin "3") (pinfunction "A_3") (pintype "input"))
    )
    (net (code "110") (name "Net-(U301-FB)") (class "Default")
      (node (ref "R303") (pin "P$1") (pinfunction "P$1_P$1") (pintype "bidirectional"))
      (node (ref "R304") (pin "P$2") (pinfunction "P$2_P$2") (pintype "bidirectional"))
      (node (ref "U301") (pin "1") (pinfunction "FB_1") (pintype "bidirectional"))
    )
    (net (code "111") (name "Net-(U301-ISET)") (class "Default")
      (node (ref "R301") (pin "P$1") (pinfunction "P$1_P$1") (pintype "bidirectional"))
      (node (ref "R302") (pin "P$2") (pinfunction "P$2_P$2") (pintype "bidirectional"))
      (node (ref "U301") (pin "3") (pinfunction "ISET_3") (pintype "bidirectional"))
    )
    (net (code "112") (name "Net-(U401-VDDA)") (class "Default")
      (node (ref "C417") (pin "P$1") (pinfunction "P$1_P$1") (pintype "bidirectional"))
      (node (ref "D401") (pin "C") (pinfunction "C_C") (pintype "passive"))
      (node (ref "U401") (pin "16") (pinfunction "VDDA_16") (pintype "bidirectional"))
    )
    (net (code "113") (name "Net-(U401-VOA)") (class "Default")
      (node (ref "R413") (pin "P$1") (pinfunction "P$1_P$1") (pintype "bidirectional"))
      (node (ref "U401") (pin "15") (pinfunction "VOA_15") (pintype "bidirectional"))
    )
    (net (code "114") (name "Net-(U401-VOB)") (class "Default")
      (node (ref "R417") (pin "P$1") (pinfunction "P$1_P$1") (pintype "bidirectional"))
      (node (ref "U401") (pin "10") (pinfunction "VOB_10") (pintype "bidirectional"))
    )
    (net (code "115") (name "Net-(U402-VDDA)") (class "Default")
      (node (ref "C418") (pin "P$1") (pinfunction "P$1_P$1") (pintype "bidirectional"))
      (node (ref "D402") (pin "C") (pinfunction "C_C") (pintype "passive"))
      (node (ref "U402") (pin "16") (pinfunction "VDDA_16") (pintype "bidirectional"))
    )
    (net (code "116") (name "Net-(U402-VOA)") (class "Default")
      (node (ref "R414") (pin "P$1") (pinfunction "P$1_P$1") (pintype "bidirectional"))
      (node (ref "U402") (pin "15") (pinfunction "VOA_15") (pintype "bidirectional"))
    )
    (net (code "117") (name "Net-(U402-VOB)") (class "Default")
      (node (ref "R418") (pin "P$1") (pinfunction "P$1_P$1") (pintype "bidirectional"))
      (node (ref "U402") (pin "10") (pinfunction "VOB_10") (pintype "bidirectional"))
    )
    (net (code "118") (name "Net-(U403-VDDA)") (class "Default")
      (node (ref "C419") (pin "P$1") (pinfunction "P$1_P$1") (pintype "bidirectional"))
      (node (ref "D403") (pin "C") (pinfunction "C_C") (pintype "passive"))
      (node (ref "U403") (pin "16") (pinfunction "VDDA_16") (pintype "bidirectional"))
    )
    (net (code "119") (name "Net-(U403-VOA)") (class "Default")
      (node (ref "R415") (pin "P$1") (pinfunction "P$1_P$1") (pintype "bidirectional"))
      (node (ref "U403") (pin "15") (pinfunction "VOA_15") (pintype "bidirectional"))
    )
    (net (code "120") (name "Net-(U403-VOB)") (class "Default")
      (node (ref "R419") (pin "P$1") (pinfunction "P$1_P$1") (pintype "bidirectional"))
      (node (ref "U403") (pin "10") (pinfunction "VOB_10") (pintype "bidirectional"))
    )
    (net (code "121") (name "Net-(U404-VDDA)") (class "Default")
      (node (ref "C420") (pin "P$1") (pinfunction "P$1_P$1") (pintype "bidirectional"))
      (node (ref "D404") (pin "C") (pinfunction "C_C") (pintype "passive"))
      (node (ref "U404") (pin "16") (pinfunction "VDDA_16") (pintype "bidirectional"))
    )
    (net (code "122") (name "Net-(U404-VOA)") (class "Default")
      (node (ref "R416") (pin "P$1") (pinfunction "P$1_P$1") (pintype "bidirectional"))
      (node (ref "U404") (pin "15") (pinfunction "VOA_15") (pintype "bidirectional"))
    )
    (net (code "123") (name "Net-(U404-VOB)") (class "Default")
      (node (ref "R420") (pin "P$1") (pinfunction "P$1_P$1") (pintype "bidirectional"))
      (node (ref "U404") (pin "10") (pinfunction "VOB_10") (pintype "bidirectional"))
    )
    (net (code "124") (name "Net-(U405E-IN+)") (class "Default")
      (node (ref "C427") (pin "P$2") (pinfunction "P$2_P$2") (pintype "bidirectional"))
      (node (ref "C428") (pin "P$1") (pinfunction "P$1_P$1") (pintype "bidirectional"))
      (node (ref "R424") (pin "P$2") (pinfunction "P$2_P$2") (pintype "bidirectional"))
      (node (ref "U405") (pin "8") (pinfunction "IN+_8") (pintype "bidirectional"))
    )
    (net (code "125") (name "Net-(U405E-IN-)") (class "Default")
      (node (ref "C426") (pin "P$2") (pinfunction "P$2_P$2") (pintype "bidirectional"))
      (node (ref "C427") (pin "P$1") (pinfunction "P$1_P$1") (pintype "bidirectional"))
      (node (ref "R423") (pin "P$2") (pinfunction "P$2_P$2") (pintype "bidirectional"))
      (node (ref "U405") (pin "1") (pinfunction "IN-_1") (pintype "bidirectional"))
    )
    (net (code "126") (name "Net-(U406E-IN+)") (class "Default")
      (node (ref "C430") (pin "P$2") (pinfunction "P$2_P$2") (pintype "bidirectional"))
      (node (ref "C431") (pin "P$1") (pinfunction "P$1_P$1") (pintype "bidirectional"))
      (node (ref "R426") (pin "P$2") (pinfunction "P$2_P$2") (pintype "bidirectional"))
      (node (ref "U406") (pin "8") (pinfunction "IN+_8") (pintype "bidirectional"))
    )
    (net (code "127") (name "Net-(U406E-IN-)") (class "Default")
      (node (ref "C429") (pin "P$2") (pinfunction "P$2_P$2") (pintype "bidirectional"))
      (node (ref "C430") (pin "P$1") (pinfunction "P$1_P$1") (pintype "bidirectional"))
      (node (ref "R425") (pin "P$2") (pinfunction "P$2_P$2") (pintype "bidirectional"))
      (node (ref "U406") (pin "1") (pinfunction "IN-_1") (pintype "bidirectional"))
    )
    (net (code "128") (name "Net-(U407-AN)") (class "Default")
      (node (ref "R429") (pin "P$1") (pinfunction "P$1_P$1") (pintype "bidirectional"))
      (node (ref "U407") (pin "2") (pinfunction "AN_2") (pintype "bidirectional"))
    )
    (net (code "129") (name "Net-(U501-(CTS)GPIO4-~{CS4}-EVTCNTR)") (class "Default")
      (node (ref "JP507") (pin "1") (pinfunction "1_1") (pintype "passive"))
      (node (ref "U501") (pin "18") (pinfunction "(CTS)GPIO4-~{CS4}-EVTCNTR_18") (pintype "bidirectional"))
    )
    (net (code "130") (name "Net-(U501-(DCD)MISO)") (class "Default")
      (node (ref "JP501") (pin "1") (pinfunction "1_1") (pintype "passive"))
      (node (ref "U501") (pin "24") (pinfunction "(DCD)MISO_24") (pintype "bidirectional"))
    )
    (net (code "131") (name "Net-(U501-(DSR)GPIO0-~{CS0})") (class "Default")
      (node (ref "JP504") (pin "1") (pinfunction "1_1") (pintype "passive"))
      (node (ref "U501") (pin "22") (pinfunction "(DSR)GPIO0-~{CS0}_22") (pintype "bidirectional"))
    )
    (net (code "132") (name "Net-(U501-(DTR)MOSI)") (class "Default")
      (node (ref "JP502") (pin "1") (pinfunction "1_1") (pintype "passive"))
      (node (ref "U501") (pin "23") (pinfunction "(DTR)MOSI_23") (pintype "bidirectional"))
    )
    (net (code "133") (name "Net-(U501-(RI{slash}CLK)SCK)") (class "Default")
      (node (ref "JP503") (pin "1") (pinfunction "1_1") (pintype "passive"))
      (node (ref "U501") (pin "1") (pinfunction "(RI/CLK)SCK_1") (pintype "bidirectional"))
    )
    (net (code "134") (name "Net-(U501-(RXD)GPIO2-~{CS2})") (class "Default")
      (node (ref "JP506") (pin "1") (pinfunction "1_1") (pintype "passive"))
      (node (ref "U501") (pin "20") (pinfunction "(RXD)GPIO2-~{CS2}_20") (pintype "bidirectional"))
    )
    (net (code "135") (name "Net-(U501-(TXD)GPIO1-~{CS1})") (class "Default")
      (node (ref "JP505") (pin "1") (pinfunction "1_1") (pintype "passive"))
      (node (ref "U501") (pin "21") (pinfunction "(TXD)GPIO1-~{CS1}_21") (pintype "bidirectional"))
    )
    (net (code "136") (name "Net-(U501-VPP)") (class "Default")
      (node (ref "C503") (pin "P$1") (pinfunction "P$1_P$1") (pintype "bidirectional"))
      (node (ref "U501") (pin "16") (pinfunction "VPP_16") (pintype "bidirectional"))
    )
    (net (code "137") (name "Net-(U501-~{RST})") (class "Default")
      (node (ref "R501") (pin "P$2") (pinfunction "P$2_P$2") (pintype "bidirectional"))
      (node (ref "U501") (pin "9") (pinfunction "~{RST}_9") (pintype "bidirectional"))
    )
    (net (code "138") (name "PWM_IN") (class "Default")
      (node (ref "D504") (pin "P$3") (pinfunction "3_P$3") (pintype "bidirectional"))
      (node (ref "R504") (pin "P$2") (pinfunction "P$2_P$2") (pintype "bidirectional"))
      (node (ref "R505") (pin "P$2") (pinfunction "P$2_P$2") (pintype "bidirectional"))
      (node (ref "U102") (pin "58") (pinfunction "PWM_IN_58") (pintype "bidirectional"))
    )
    (net (code "139") (name "PWM_UX1_H") (class "Default")
      (node (ref "R405") (pin "P$2") (pinfunction "P$2_P$2") (pintype "bidirectional"))
      (node (ref "U102") (pin "39") (pinfunction "PWM_UX1_H_39") (pintype "bidirectional"))
      (node (ref "U401") (pin "1") (pinfunction "VIA_1") (pintype "bidirectional"))
    )
    (net (code "140") (name "PWM_UX1_L") (class "Default")
      (node (ref "R401") (pin "P$2") (pinfunction "P$2_P$2") (pintype "bidirectional"))
      (node (ref "U102") (pin "40") (pinfunction "PWM_UX1_L_40") (pintype "bidirectional"))
      (node (ref "U401") (pin "2") (pinfunction "VIB_2") (pintype "bidirectional"))
    )
    (net (code "141") (name "PWM_VX2_H") (class "Default")
      (node (ref "R406") (pin "P$2") (pinfunction "P$2_P$2") (pintype "bidirectional"))
      (node (ref "U102") (pin "41") (pinfunction "PWM_VX2_H_41") (pintype "bidirectional"))
      (node (ref "U402") (pin "1") (pinfunction "VIA_1") (pintype "bidirectional"))
    )
    (net (code "142") (name "PWM_VX2_L") (class "Default")
      (node (ref "R402") (pin "P$2") (pinfunction "P$2_P$2") (pintype "bidirectional"))
      (node (ref "U102") (pin "42") (pinfunction "PWM_VX2_L_42") (pintype "bidirectional"))
      (node (ref "U402") (pin "2") (pinfunction "VIB_2") (pintype "bidirectional"))
    )
    (net (code "143") (name "PWM_WY1_H") (class "Default")
      (node (ref "R407") (pin "P$2") (pinfunction "P$2_P$2") (pintype "bidirectional"))
      (node (ref "U102") (pin "46") (pinfunction "PWM_WY1_H_46") (pintype "bidirectional"))
      (node (ref "U403") (pin "1") (pinfunction "VIA_1") (pintype "bidirectional"))
    )
    (net (code "144") (name "PWM_WY1_L") (class "Default")
      (node (ref "R403") (pin "P$2") (pinfunction "P$2_P$2") (pintype "bidirectional"))
      (node (ref "U102") (pin "47") (pinfunction "PWM_WY1_L_47") (pintype "bidirectional"))
      (node (ref "U403") (pin "2") (pinfunction "VIB_2") (pintype "bidirectional"))
    )
    (net (code "145") (name "PWM_Y2_H") (class "Default")
      (node (ref "R408") (pin "P$2") (pinfunction "P$2_P$2") (pintype "bidirectional"))
      (node (ref "U102") (pin "48") (pinfunction "PWM_Y2_H_48") (pintype "bidirectional"))
      (node (ref "U404") (pin "1") (pinfunction "VIA_1") (pintype "bidirectional"))
    )
    (net (code "146") (name "PWM_Y2_L") (class "Default")
      (node (ref "R404") (pin "P$2") (pinfunction "P$2_P$2") (pintype "bidirectional"))
      (node (ref "U102") (pin "49") (pinfunction "PWM_Y2_L_49") (pintype "bidirectional"))
      (node (ref "U404") (pin "2") (pinfunction "VIB_2") (pintype "bidirectional"))
    )
    (net (code "147") (name "REF_H") (class "Default")
      (node (ref "U102") (pin "68") (pinfunction "REF_H_68") (pintype "bidirectional"))
      (node (ref "U208") (pin "5") (pinfunction "Y_5") (pintype "output"))
    )
    (net (code "148") (name "REF_L") (class "Default")
      (node (ref "U102") (pin "67") (pinfunction "REF_L_67") (pintype "bidirectional"))
      (node (ref "U208") (pin "2") (pinfunction "Y_2") (pintype "output"))
    )
    (net (code "149") (name "REF_R") (class "Default")
      (node (ref "U102") (pin "69") (pinfunction "REF_R_69") (pintype "bidirectional"))
      (node (ref "U208") (pin "7") (pinfunction "Y_7") (pintype "output"))
    )
    (net (code "150") (name "SCK") (class "Default")
      (node (ref "J501") (pin "2") (pinfunction "S_2") (pintype "passive"))
      (node (ref "JP503") (pin "2") (pinfunction "2_2") (pintype "passive"))
      (node (ref "U102") (pin "7") (pinfunction "SPI_SCK_7") (pintype "bidirectional"))
    )
    (net (code "151") (name "STEP") (class "Default")
      (node (ref "D506") (pin "P$3") (pinfunction "3_P$3") (pintype "bidirectional"))
      (node (ref "R509") (pin "P$2") (pinfunction "P$2_P$2") (pintype "bidirectional"))
      (node (ref "R510") (pin "P$2") (pinfunction "P$2_P$2") (pintype "bidirectional"))
      (node (ref "U102") (pin "57") (pinfunction "STP_57") (pintype "bidirectional"))
    )
    (net (code "152") (name "UX1") (class "Default")
      (node (ref "C417") (pin "P$2") (pinfunction "P$2_P$2") (pintype "bidirectional"))
      (node (ref "Q401") (pin "S1") (pinfunction "S1_S1") (pintype "bidirectional"))
      (node (ref "Q401") (pin "S2") (pinfunction "S1_S2") (pintype "bidirectional"))
      (node (ref "Q401") (pin "S3") (pinfunction "S1_S3") (pintype "bidirectional"))
      (node (ref "Q401") (pin "S4") (pinfunction "S1_S4") (pintype "bidirectional"))
      (node (ref "Q401") (pin "S5") (pinfunction "S1_S5") (pintype "bidirectional"))
      (node (ref "Q405") (pin "D1") (pinfunction "D1_D1") (pintype "bidirectional"))
      (node (ref "Q405") (pin "D2") (pinfunction "D1_D2") (pintype "bidirectional"))
      (node (ref "Q405") (pin "D3") (pinfunction "D1_D3") (pintype "bidirectional"))
      (node (ref "Q405") (pin "D4") (pinfunction "D1_D4") (pintype "bidirectional"))
      (node (ref "R421") (pin "1") (pinfunction "P$1_1") (pintype "bidirectional"))
      (node (ref "R421") (pin "2") (pinfunction "P$1_2") (pintype "bidirectional"))
      (node (ref "U401") (pin "14") (pinfunction "GNDA_14") (pintype "bidirectional"))
    )
    (net (code "153") (name "UX1@J401") (class "Default")
      (node (ref "J401") (pin "1") (pinfunction "S_1") (pintype "passive"))
      (node (ref "P403") (pin "H1") (pinfunction "S_H1") (pintype "passive"))
      (node (ref "P403") (pin "H10") (pinfunction "S_H10") (pintype "passive"))
      (node (ref "P403") (pin "H11") (pinfunction "S_H11") (pintype "passive"))
      (node (ref "P403") (pin "H12") (pinfunction "S_H12") (pintype "passive"))
      (node (ref "P403") (pin "H2") (pinfunction "S_H2") (pintype "passive"))
      (node (ref "P403") (pin "H3") (pinfunction "S_H3") (pintype "passive"))
      (node (ref "P403") (pin "H4") (pinfunction "S_H4") (pintype "passive"))
      (node (ref "P403") (pin "H5") (pinfunction "S_H5") (pintype "passive"))
      (node (ref "P403") (pin "H6") (pinfunction "S_H6") (pintype "passive"))
      (node (ref "P403") (pin "H7") (pinfunction "S_H7") (pintype "passive"))
      (node (ref "P403") (pin "H8") (pinfunction "S_H8") (pintype "passive"))
      (node (ref "P403") (pin "H9") (pinfunction "S_H9") (pintype "passive"))
      (node (ref "P403") (pin "PAD") (pinfunction "S_PAD") (pintype "passive"))
      (node (ref "R421") (pin "3") (pinfunction "P$2_3") (pintype "bidirectional"))
      (node (ref "R421") (pin "4") (pinfunction "P$2_4") (pintype "bidirectional"))
    )
    (net (code "154") (name "VBUS") (class "Default")
      (node (ref "R506") (pin "P$2") (pinfunction "P$2_P$2") (pintype "bidirectional"))
      (node (ref "R507") (pin "P$1") (pinfunction "P$1_P$1") (pintype "bidirectional"))
      (node (ref "U501") (pin "8") (pinfunction "VBUS_8") (pintype "bidirectional"))
    )
    (net (code "155") (name "VX2") (class "Default")
      (node (ref "C418") (pin "P$2") (pinfunction "P$2_P$2") (pintype "bidirectional"))
      (node (ref "J401") (pin "2") (pinfunction "S_2") (pintype "passive"))
      (node (ref "P401") (pin "H1") (pinfunction "S_H1") (pintype "passive"))
      (node (ref "P401") (pin "H10") (pinfunction "S_H10") (pintype "passive"))
      (node (ref "P401") (pin "H11") (pinfunction "S_H11") (pintype "passive"))
      (node (ref "P401") (pin "H12") (pinfunction "S_H12") (pintype "passive"))
      (node (ref "P401") (pin "H2") (pinfunction "S_H2") (pintype "passive"))
      (node (ref "P401") (pin "H3") (pinfunction "S_H3") (pintype "passive"))
      (node (ref "P401") (pin "H4") (pinfunction "S_H4") (pintype "passive"))
      (node (ref "P401") (pin "H5") (pinfunction "S_H5") (pintype "passive"))
      (node (ref "P401") (pin "H6") (pinfunction "S_H6") (pintype "passive"))
      (node (ref "P401") (pin "H7") (pinfunction "S_H7") (pintype "passive"))
      (node (ref "P401") (pin "H8") (pinfunction "S_H8") (pintype "passive"))
      (node (ref "P401") (pin "H9") (pinfunction "S_H9") (pintype "passive"))
      (node (ref "P401") (pin "PAD") (pinfunction "S_PAD") (pintype "passive"))
      (node (ref "Q402") (pin "S1") (pinfunction "S1_S1") (pintype "bidirectional"))
      (node (ref "Q402") (pin "S2") (pinfunction "S1_S2") (pintype "bidirectional"))
      (node (ref "Q402") (pin "S3") (pinfunction "S1_S3") (pintype "bidirectional"))
      (node (ref "Q402") (pin "S4") (pinfunction "S1_S4") (pintype "bidirectional"))
      (node (ref "Q402") (pin "S5") (pinfunction "S1_S5") (pintype "bidirectional"))
      (node (ref "Q406") (pin "D1") (pinfunction "D1_D1") (pintype "bidirectional"))
      (node (ref "Q406") (pin "D2") (pinfunction "D1_D2") (pintype "bidirectional"))
      (node (ref "Q406") (pin "D3") (pinfunction "D1_D3") (pintype "bidirectional"))
      (node (ref "Q406") (pin "D4") (pinfunction "D1_D4") (pintype "bidirectional"))
      (node (ref "U402") (pin "14") (pinfunction "GNDA_14") (pintype "bidirectional"))
    )
    (net (code "156") (name "WY1") (class "Default")
      (node (ref "C419") (pin "P$2") (pinfunction "P$2_P$2") (pintype "bidirectional"))
      (node (ref "Q403") (pin "S1") (pinfunction "S1_S1") (pintype "bidirectional"))
      (node (ref "Q403") (pin "S2") (pinfunction "S1_S2") (pintype "bidirectional"))
      (node (ref "Q403") (pin "S3") (pinfunction "S1_S3") (pintype "bidirectional"))
      (node (ref "Q403") (pin "S4") (pinfunction "S1_S4") (pintype "bidirectional"))
      (node (ref "Q403") (pin "S5") (pinfunction "S1_S5") (pintype "bidirectional"))
      (node (ref "Q407") (pin "D1") (pinfunction "D1_D1") (pintype "bidirectional"))
      (node (ref "Q407") (pin "D2") (pinfunction "D1_D2") (pintype "bidirectional"))
      (node (ref "Q407") (pin "D3") (pinfunction "D1_D3") (pintype "bidirectional"))
      (node (ref "Q407") (pin "D4") (pinfunction "D1_D4") (pintype "bidirectional"))
      (node (ref "R422") (pin "1") (pinfunction "P$1_1") (pintype "bidirectional"))
      (node (ref "R422") (pin "2") (pinfunction "P$1_2") (pintype "bidirectional"))
      (node (ref "U403") (pin "14") (pinfunction "GNDA_14") (pintype "bidirectional"))
    )
    (net (code "157") (name "WY1@J401") (class "Default")
      (node (ref "J401") (pin "3") (pinfunction "S_3") (pintype "passive"))
      (node (ref "P404") (pin "H1") (pinfunction "S_H1") (pintype "passive"))
      (node (ref "P404") (pin "H10") (pinfunction "S_H10") (pintype "passive"))
      (node (ref "P404") (pin "H11") (pinfunction "S_H11") (pintype "passive"))
      (node (ref "P404") (pin "H12") (pinfunction "S_H12") (pintype "passive"))
      (node (ref "P404") (pin "H2") (pinfunction "S_H2") (pintype "passive"))
      (node (ref "P404") (pin "H3") (pinfunction "S_H3") (pintype "passive"))
      (node (ref "P404") (pin "H4") (pinfunction "S_H4") (pintype "passive"))
      (node (ref "P404") (pin "H5") (pinfunction "S_H5") (pintype "passive"))
      (node (ref "P404") (pin "H6") (pinfunction "S_H6") (pintype "passive"))
      (node (ref "P404") (pin "H7") (pinfunction "S_H7") (pintype "passive"))
      (node (ref "P404") (pin "H8") (pinfunction "S_H8") (pintype "passive"))
      (node (ref "P404") (pin "H9") (pinfunction "S_H9") (pintype "passive"))
      (node (ref "P404") (pin "PAD") (pinfunction "S_PAD") (pintype "passive"))
      (node (ref "R422") (pin "3") (pinfunction "P$2_3") (pintype "bidirectional"))
      (node (ref "R422") (pin "4") (pinfunction "P$2_4") (pintype "bidirectional"))
    )
    (net (code "158") (name "Y2") (class "Default")
      (node (ref "C420") (pin "P$2") (pinfunction "P$2_P$2") (pintype "bidirectional"))
      (node (ref "J401") (pin "4") (pinfunction "S_4") (pintype "passive"))
      (node (ref "P402") (pin "H1") (pinfunction "S_H1") (pintype "passive"))
      (node (ref "P402") (pin "H10") (pinfunction "S_H10") (pintype "passive"))
      (node (ref "P402") (pin "H11") (pinfunction "S_H11") (pintype "passive"))
      (node (ref "P402") (pin "H12") (pinfunction "S_H12") (pintype "passive"))
      (node (ref "P402") (pin "H2") (pinfunction "S_H2") (pintype "passive"))
      (node (ref "P402") (pin "H3") (pinfunction "S_H3") (pintype "passive"))
      (node (ref "P402") (pin "H4") (pinfunction "S_H4") (pintype "passive"))
      (node (ref "P402") (pin "H5") (pinfunction "S_H5") (pintype "passive"))
      (node (ref "P402") (pin "H6") (pinfunction "S_H6") (pintype "passive"))
      (node (ref "P402") (pin "H7") (pinfunction "S_H7") (pintype "passive"))
      (node (ref "P402") (pin "H8") (pinfunction "S_H8") (pintype "passive"))
      (node (ref "P402") (pin "H9") (pinfunction "S_H9") (pintype "passive"))
      (node (ref "P402") (pin "PAD") (pinfunction "S_PAD") (pintype "passive"))
      (node (ref "Q404") (pin "S1") (pinfunction "S1_S1") (pintype "bidirectional"))
      (node (ref "Q404") (pin "S2") (pinfunction "S1_S2") (pintype "bidirectional"))
      (node (ref "Q404") (pin "S3") (pinfunction "S1_S3") (pintype "bidirectional"))
      (node (ref "Q404") (pin "S4") (pinfunction "S1_S4") (pintype "bidirectional"))
      (node (ref "Q404") (pin "S5") (pinfunction "S1_S5") (pintype "bidirectional"))
      (node (ref "Q408") (pin "D1") (pinfunction "D1_D1") (pintype "bidirectional"))
      (node (ref "Q408") (pin "D2") (pinfunction "D1_D2") (pintype "bidirectional"))
      (node (ref "Q408") (pin "D3") (pinfunction "D1_D3") (pintype "bidirectional"))
      (node (ref "Q408") (pin "D4") (pinfunction "D1_D4") (pintype "bidirectional"))
      (node (ref "U404") (pin "14") (pinfunction "GNDA_14") (pintype "bidirectional"))
    )
    (net (code "159") (name "unconnected-(J505C-S-Pad2)") (class "Default")
      (node (ref "J505") (pin "2") (pinfunction "S_2") (pintype "passive"))
    )
    (net (code "160") (name "unconnected-(U102A-ENI-Pad55)") (class "Default")
      (node (ref "U102") (pin "55") (pinfunction "ENI_55") (pintype "bidirectional"))
    )
    (net (code "161") (name "unconnected-(U102A-GPIO0-Pad70)") (class "Default")
      (node (ref "U102") (pin "70") (pinfunction "GPIO0_70") (pintype "bidirectional"))
    )
    (net (code "162") (name "unconnected-(U102A-GPIO1-Pad71)") (class "Default")
      (node (ref "U102") (pin "71") (pinfunction "GPIO1_71") (pintype "bidirectional"))
    )
    (net (code "163") (name "unconnected-(U102A-GPIO2-Pad74)") (class "Default")
      (node (ref "U102") (pin "74") (pinfunction "GPIO2_74") (pintype "bidirectional"))
    )
    (net (code "164") (name "unconnected-(U201-Pad3)") (class "Default")
      (node (ref "U201") (pin "3") (pinfunction "3_3") (pintype "bidirectional"))
    )
    (net (code "165") (name "unconnected-(U202-Pad3)") (class "Default")
      (node (ref "U202") (pin "3") (pinfunction "3_3") (pintype "bidirectional"))
    )
    (net (code "166") (name "unconnected-(U203-Pad3)") (class "Default")
      (node (ref "U203") (pin "3") (pinfunction "3_3") (pintype "bidirectional"))
    )
    (net (code "167") (name "unconnected-(U204-Pad3)") (class "Default")
      (node (ref "U204") (pin "3") (pinfunction "3_3") (pintype "bidirectional"))
    )
    (net (code "168") (name "unconnected-(U501-(GPIO2-RS485)GPIO9-~{CS9}-SUSPEND-Pad12)") (class "Default")
      (node (ref "U501") (pin "12") (pinfunction "(GPIO2-RS485)GPIO9-~{CS9}-SUSPEND_12") (pintype "bidirectional"))
    )
    (net (code "169") (name "unconnected-(U501-(GPIO3-WKUP)GPIO10-~{CS10}-~{SUSPEND}-Pad11)") (class "Default")
      (node (ref "U501") (pin "11") (pinfunction "(GPIO3-WKUP)GPIO10-~{CS10}-~{SUSPEND}_11") (pintype "bidirectional"))
    )
    (net (code "170") (name "unconnected-(U501-(RTS)GPIO3-~{CS3}-RTR-Pad19)") (class "Default")
      (node (ref "U501") (pin "19") (pinfunction "(RTS)GPIO3-~{CS3}-RTR_19") (pintype "bidirectional"))
    )
    (net (code "171") (name "unconnected-(U501-(SUSPEND)GPIO5-~{CS5}-CLKOUT-Pad17)") (class "Default")
      (node (ref "U501") (pin "17") (pinfunction "(SUSPEND)GPIO5-~{CS5}-CLKOUT_17") (pintype "bidirectional"))
    )
    (net (code "172") (name "unconnected-(U501-(~{SUSPEND})GPIO6-~{CS6}-Pad15)") (class "Default")
      (node (ref "U501") (pin "15") (pinfunction "(~{SUSPEND})GPIO6-~{CS6}_15") (pintype "bidirectional"))
    )
    (net (code "173") (name "~{CS}") (class "Default")
      (node (ref "J501") (pin "1") (pinfunction "S_1") (pintype "passive"))
      (node (ref "JP504") (pin "2") (pinfunction "2_2") (pintype "passive"))
      (node (ref "U102") (pin "6") (pinfunction "SPI_NSCS_6") (pintype "bidirectional"))
    )
  )
)
